# proto.net
KiCad netlist of a schematic drawn in EAGLE
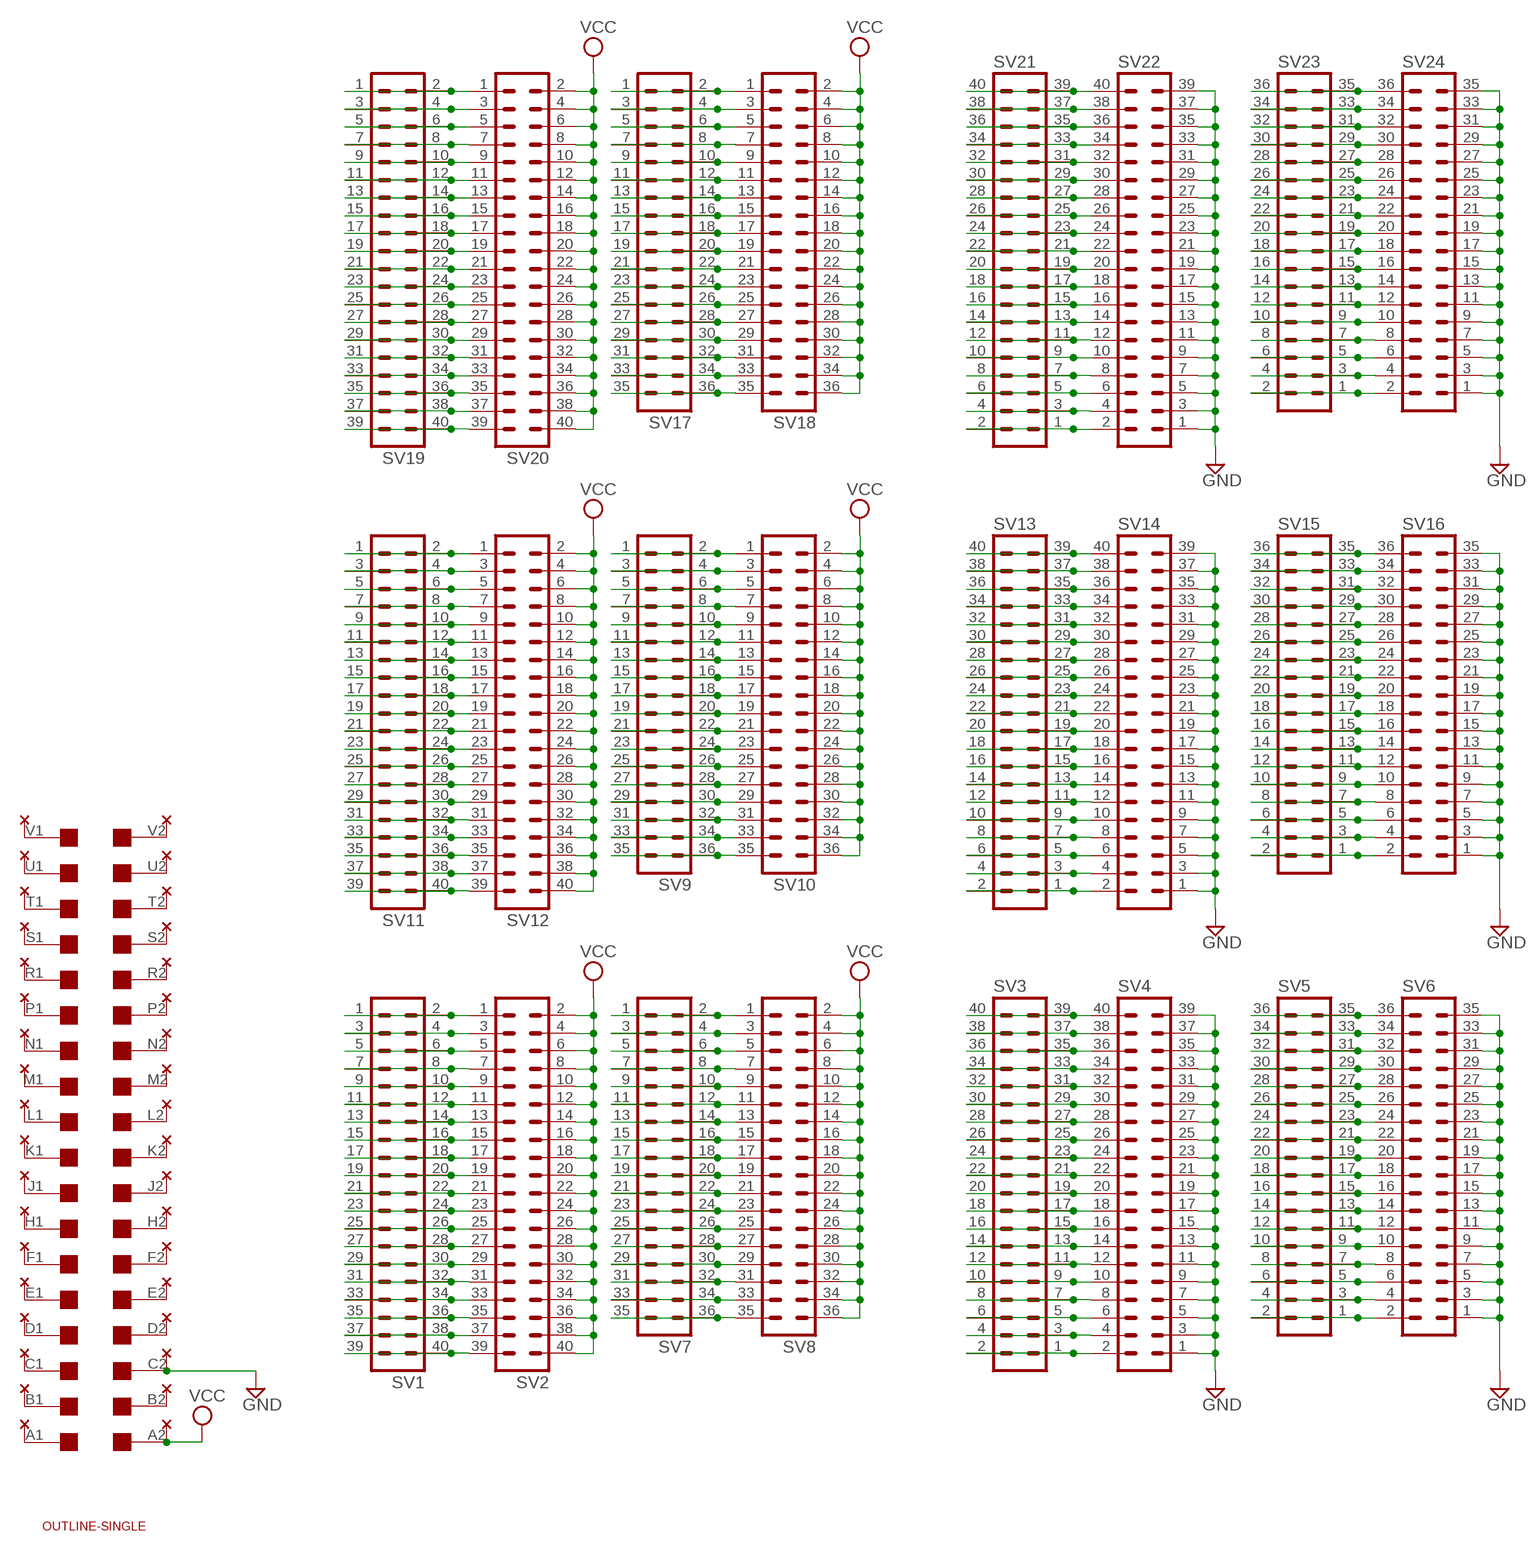
[diagram p0: schematic, sheet 1]

(export (version "E")
  (design (tool "Eeschema 10.0.6"))
  (components
    (comp (ref "SV1")
      (value "MA20-2")
      (footprint "eagle-import:MA20-2")
      (libsource (lib "eagle-import") (part "MA20-2"))
    )
    (comp (ref "SV2")
      (value "MA20-2")
      (footprint "eagle-import:MA20-2")
      (libsource (lib "eagle-import") (part "MA20-2"))
    )
    (comp (ref "SV3")
      (value "MA20-2")
      (footprint "eagle-import:MA20-2")
      (libsource (lib "eagle-import") (part "MA20-2"))
    )
    (comp (ref "SV4")
      (value "MA20-2")
      (footprint "eagle-import:MA20-2")
      (libsource (lib "eagle-import") (part "MA20-2"))
    )
    (comp (ref "SV5")
      (value "MA18-2")
      (footprint "eagle-import:MA18-2")
      (libsource (lib "eagle-import") (part "MA18-2"))
    )
    (comp (ref "SV6")
      (value "MA18-2")
      (footprint "eagle-import:MA18-2")
      (libsource (lib "eagle-import") (part "MA18-2"))
    )
    (comp (ref "SV7")
      (value "MA18-2")
      (footprint "eagle-import:MA18-2")
      (libsource (lib "eagle-import") (part "MA18-2"))
    )
    (comp (ref "SV8")
      (value "MA18-2")
      (footprint "eagle-import:MA18-2")
      (libsource (lib "eagle-import") (part "MA18-2"))
    )
    (comp (ref "SV9")
      (value "MA18-2")
      (footprint "eagle-import:MA18-2")
      (libsource (lib "eagle-import") (part "MA18-2"))
    )
    (comp (ref "SV10")
      (value "MA18-2")
      (footprint "eagle-import:MA18-2")
      (libsource (lib "eagle-import") (part "MA18-2"))
    )
    (comp (ref "SV11")
      (value "MA20-2")
      (footprint "eagle-import:MA20-2")
      (libsource (lib "eagle-import") (part "MA20-2"))
    )
    (comp (ref "SV12")
      (value "MA20-2")
      (footprint "eagle-import:MA20-2")
      (libsource (lib "eagle-import") (part "MA20-2"))
    )
    (comp (ref "SV13")
      (value "MA20-2")
      (footprint "eagle-import:MA20-2")
      (libsource (lib "eagle-import") (part "MA20-2"))
    )
    (comp (ref "SV14")
      (value "MA20-2")
      (footprint "eagle-import:MA20-2")
      (libsource (lib "eagle-import") (part "MA20-2"))
    )
    (comp (ref "SV15")
      (value "MA18-2")
      (footprint "eagle-import:MA18-2")
      (libsource (lib "eagle-import") (part "MA18-2"))
    )
    (comp (ref "SV16")
      (value "MA18-2")
      (footprint "eagle-import:MA18-2")
      (libsource (lib "eagle-import") (part "MA18-2"))
    )
    (comp (ref "SV17")
      (value "MA18-2")
      (footprint "eagle-import:MA18-2")
      (libsource (lib "eagle-import") (part "MA18-2"))
    )
    (comp (ref "SV18")
      (value "MA18-2")
      (footprint "eagle-import:MA18-2")
      (libsource (lib "eagle-import") (part "MA18-2"))
    )
    (comp (ref "SV19")
      (value "MA20-2")
      (footprint "eagle-import:MA20-2")
      (libsource (lib "eagle-import") (part "MA20-2"))
    )
    (comp (ref "SV20")
      (value "MA20-2")
      (footprint "eagle-import:MA20-2")
      (libsource (lib "eagle-import") (part "MA20-2"))
    )
    (comp (ref "SV21")
      (value "MA20-2")
      (footprint "eagle-import:MA20-2")
      (libsource (lib "eagle-import") (part "MA20-2"))
    )
    (comp (ref "SV22")
      (value "MA20-2")
      (footprint "eagle-import:MA20-2")
      (libsource (lib "eagle-import") (part "MA20-2"))
    )
    (comp (ref "SV23")
      (value "MA18-2")
      (footprint "eagle-import:MA18-2")
      (libsource (lib "eagle-import") (part "MA18-2"))
    )
    (comp (ref "SV24")
      (value "MA18-2")
      (footprint "eagle-import:MA18-2")
      (libsource (lib "eagle-import") (part "MA18-2"))
    )
    (comp (ref "U$1")
      (value "EDGE-2CONNECTOR")
      (footprint "eagle-import:EDGE-CON2")
      (libsource (lib "eagle-import") (part "EDGE-2CONNECTOR"))
    )
    (comp (ref "U$2")
      (value "OUTLINE-SINGLE")
      (footprint "eagle-import:SINGLE")
      (libsource (lib "eagle-import") (part "OUTLINE-SINGLE"))
    )
    (comp (ref "U$3")
      (value "THRU-HOLE2A")
      (footprint "eagle-import:THRU-HOLEA")
      (libsource (lib "eagle-import") (part "THRU-HOLE2A"))
    )
  )
  (nets
    (net (code "1") (name "GND") (class "Default")
      (node (ref "SV14") (pin "1") (pinfunction "1_1") (pintype "passive"))
      (node (ref "SV14") (pin "11") (pinfunction "11_11") (pintype "passive"))
      (node (ref "SV14") (pin "13") (pinfunction "13_13") (pintype "passive"))
      (node (ref "SV14") (pin "15") (pinfunction "15_15") (pintype "passive"))
      (node (ref "SV14") (pin "17") (pinfunction "17_17") (pintype "passive"))
      (node (ref "SV14") (pin "19") (pinfunction "19_19") (pintype "passive"))
      (node (ref "SV14") (pin "21") (pinfunction "21_21") (pintype "passive"))
      (node (ref "SV14") (pin "23") (pinfunction "23_23") (pintype "passive"))
      (node (ref "SV14") (pin "25") (pinfunction "25_25") (pintype "passive"))
      (node (ref "SV14") (pin "27") (pinfunction "27_27") (pintype "passive"))
      (node (ref "SV14") (pin "29") (pinfunction "29_29") (pintype "passive"))
      (node (ref "SV14") (pin "3") (pinfunction "3_3") (pintype "passive"))
      (node (ref "SV14") (pin "31") (pinfunction "31_31") (pintype "passive"))
      (node (ref "SV14") (pin "33") (pinfunction "33_33") (pintype "passive"))
      (node (ref "SV14") (pin "35") (pinfunction "35_35") (pintype "passive"))
      (node (ref "SV14") (pin "37") (pinfunction "37_37") (pintype "passive"))
      (node (ref "SV14") (pin "39") (pinfunction "39_39") (pintype "passive"))
      (node (ref "SV14") (pin "5") (pinfunction "5_5") (pintype "passive"))
      (node (ref "SV14") (pin "7") (pinfunction "7_7") (pintype "passive"))
      (node (ref "SV14") (pin "9") (pinfunction "9_9") (pintype "passive"))
      (node (ref "SV16") (pin "1") (pinfunction "1_1") (pintype "passive"))
      (node (ref "SV16") (pin "11") (pinfunction "11_11") (pintype "passive"))
      (node (ref "SV16") (pin "13") (pinfunction "13_13") (pintype "passive"))
      (node (ref "SV16") (pin "15") (pinfunction "15_15") (pintype "passive"))
      (node (ref "SV16") (pin "17") (pinfunction "17_17") (pintype "passive"))
      (node (ref "SV16") (pin "19") (pinfunction "19_19") (pintype "passive"))
      (node (ref "SV16") (pin "21") (pinfunction "21_21") (pintype "passive"))
      (node (ref "SV16") (pin "23") (pinfunction "23_23") (pintype "passive"))
      (node (ref "SV16") (pin "25") (pinfunction "25_25") (pintype "passive"))
      (node (ref "SV16") (pin "27") (pinfunction "27_27") (pintype "passive"))
      (node (ref "SV16") (pin "29") (pinfunction "29_29") (pintype "passive"))
      (node (ref "SV16") (pin "3") (pinfunction "3_3") (pintype "passive"))
      (node (ref "SV16") (pin "31") (pinfunction "31_31") (pintype "passive"))
      (node (ref "SV16") (pin "33") (pinfunction "33_33") (pintype "passive"))
      (node (ref "SV16") (pin "35") (pinfunction "35_35") (pintype "passive"))
      (node (ref "SV16") (pin "5") (pinfunction "5_5") (pintype "passive"))
      (node (ref "SV16") (pin "7") (pinfunction "7_7") (pintype "passive"))
      (node (ref "SV16") (pin "9") (pinfunction "9_9") (pintype "passive"))
      (node (ref "SV22") (pin "1") (pinfunction "1_1") (pintype "passive"))
      (node (ref "SV22") (pin "11") (pinfunction "11_11") (pintype "passive"))
      (node (ref "SV22") (pin "13") (pinfunction "13_13") (pintype "passive"))
      (node (ref "SV22") (pin "15") (pinfunction "15_15") (pintype "passive"))
      (node (ref "SV22") (pin "17") (pinfunction "17_17") (pintype "passive"))
      (node (ref "SV22") (pin "19") (pinfunction "19_19") (pintype "passive"))
      (node (ref "SV22") (pin "21") (pinfunction "21_21") (pintype "passive"))
      (node (ref "SV22") (pin "23") (pinfunction "23_23") (pintype "passive"))
      (node (ref "SV22") (pin "25") (pinfunction "25_25") (pintype "passive"))
      (node (ref "SV22") (pin "27") (pinfunction "27_27") (pintype "passive"))
      (node (ref "SV22") (pin "29") (pinfunction "29_29") (pintype "passive"))
      (node (ref "SV22") (pin "3") (pinfunction "3_3") (pintype "passive"))
      (node (ref "SV22") (pin "31") (pinfunction "31_31") (pintype "passive"))
      (node (ref "SV22") (pin "33") (pinfunction "33_33") (pintype "passive"))
      (node (ref "SV22") (pin "35") (pinfunction "35_35") (pintype "passive"))
      (node (ref "SV22") (pin "37") (pinfunction "37_37") (pintype "passive"))
      (node (ref "SV22") (pin "39") (pinfunction "39_39") (pintype "passive"))
      (node (ref "SV22") (pin "5") (pinfunction "5_5") (pintype "passive"))
      (node (ref "SV22") (pin "7") (pinfunction "7_7") (pintype "passive"))
      (node (ref "SV22") (pin "9") (pinfunction "9_9") (pintype "passive"))
      (node (ref "SV24") (pin "1") (pinfunction "1_1") (pintype "passive"))
      (node (ref "SV24") (pin "11") (pinfunction "11_11") (pintype "passive"))
      (node (ref "SV24") (pin "13") (pinfunction "13_13") (pintype "passive"))
      (node (ref "SV24") (pin "15") (pinfunction "15_15") (pintype "passive"))
      (node (ref "SV24") (pin "17") (pinfunction "17_17") (pintype "passive"))
      (node (ref "SV24") (pin "19") (pinfunction "19_19") (pintype "passive"))
      (node (ref "SV24") (pin "21") (pinfunction "21_21") (pintype "passive"))
      (node (ref "SV24") (pin "23") (pinfunction "23_23") (pintype "passive"))
      (node (ref "SV24") (pin "25") (pinfunction "25_25") (pintype "passive"))
      (node (ref "SV24") (pin "27") (pinfunction "27_27") (pintype "passive"))
      (node (ref "SV24") (pin "29") (pinfunction "29_29") (pintype "passive"))
      (node (ref "SV24") (pin "3") (pinfunction "3_3") (pintype "passive"))
      (node (ref "SV24") (pin "31") (pinfunction "31_31") (pintype "passive"))
      (node (ref "SV24") (pin "33") (pinfunction "33_33") (pintype "passive"))
      (node (ref "SV24") (pin "35") (pinfunction "35_35") (pintype "passive"))
      (node (ref "SV24") (pin "5") (pinfunction "5_5") (pintype "passive"))
      (node (ref "SV24") (pin "7") (pinfunction "7_7") (pintype "passive"))
      (node (ref "SV24") (pin "9") (pinfunction "9_9") (pintype "passive"))
      (node (ref "SV4") (pin "1") (pinfunction "1_1") (pintype "passive"))
      (node (ref "SV4") (pin "11") (pinfunction "11_11") (pintype "passive"))
      (node (ref "SV4") (pin "13") (pinfunction "13_13") (pintype "passive"))
      (node (ref "SV4") (pin "15") (pinfunction "15_15") (pintype "passive"))
      (node (ref "SV4") (pin "17") (pinfunction "17_17") (pintype "passive"))
      (node (ref "SV4") (pin "19") (pinfunction "19_19") (pintype "passive"))
      (node (ref "SV4") (pin "21") (pinfunction "21_21") (pintype "passive"))
      (node (ref "SV4") (pin "23") (pinfunction "23_23") (pintype "passive"))
      (node (ref "SV4") (pin "25") (pinfunction "25_25") (pintype "passive"))
      (node (ref "SV4") (pin "27") (pinfunction "27_27") (pintype "passive"))
      (node (ref "SV4") (pin "29") (pinfunction "29_29") (pintype "passive"))
      (node (ref "SV4") (pin "3") (pinfunction "3_3") (pintype "passive"))
      (node (ref "SV4") (pin "31") (pinfunction "31_31") (pintype "passive"))
      (node (ref "SV4") (pin "33") (pinfunction "33_33") (pintype "passive"))
      (node (ref "SV4") (pin "35") (pinfunction "35_35") (pintype "passive"))
      (node (ref "SV4") (pin "37") (pinfunction "37_37") (pintype "passive"))
      (node (ref "SV4") (pin "39") (pinfunction "39_39") (pintype "passive"))
      (node (ref "SV4") (pin "5") (pinfunction "5_5") (pintype "passive"))
      (node (ref "SV4") (pin "7") (pinfunction "7_7") (pintype "passive"))
      (node (ref "SV4") (pin "9") (pinfunction "9_9") (pintype "passive"))
      (node (ref "SV6") (pin "1") (pinfunction "1_1") (pintype "passive"))
      (node (ref "SV6") (pin "11") (pinfunction "11_11") (pintype "passive"))
      (node (ref "SV6") (pin "13") (pinfunction "13_13") (pintype "passive"))
      (node (ref "SV6") (pin "15") (pinfunction "15_15") (pintype "passive"))
      (node (ref "SV6") (pin "17") (pinfunction "17_17") (pintype "passive"))
      (node (ref "SV6") (pin "19") (pinfunction "19_19") (pintype "passive"))
      (node (ref "SV6") (pin "21") (pinfunction "21_21") (pintype "passive"))
      (node (ref "SV6") (pin "23") (pinfunction "23_23") (pintype "passive"))
      (node (ref "SV6") (pin "25") (pinfunction "25_25") (pintype "passive"))
      (node (ref "SV6") (pin "27") (pinfunction "27_27") (pintype "passive"))
      (node (ref "SV6") (pin "29") (pinfunction "29_29") (pintype "passive"))
      (node (ref "SV6") (pin "3") (pinfunction "3_3") (pintype "passive"))
      (node (ref "SV6") (pin "31") (pinfunction "31_31") (pintype "passive"))
      (node (ref "SV6") (pin "33") (pinfunction "33_33") (pintype "passive"))
      (node (ref "SV6") (pin "35") (pinfunction "35_35") (pintype "passive"))
      (node (ref "SV6") (pin "5") (pinfunction "5_5") (pintype "passive"))
      (node (ref "SV6") (pin "7") (pinfunction "7_7") (pintype "passive"))
      (node (ref "SV6") (pin "9") (pinfunction "9_9") (pintype "passive"))
      (node (ref "U$1") (pin "C2") (pinfunction "1_C2") (pintype "bidirectional"))
      (node (ref "U$3") (pin "C2") (pinfunction "P$1_C2") (pintype "passive"))
    )
    (net (code "2") (name "Net-(SV1-Pad1)") (class "Default")
      (node (ref "SV1") (pin "1") (pinfunction "1_1") (pintype "passive"))
      (node (ref "SV1") (pin "2") (pinfunction "2_2") (pintype "passive"))
      (node (ref "SV2") (pin "1") (pinfunction "1_1") (pintype "passive"))
    )
    (net (code "3") (name "Net-(SV1-Pad3)") (class "Default")
      (node (ref "SV1") (pin "3") (pinfunction "3_3") (pintype "passive"))
      (node (ref "SV1") (pin "4") (pinfunction "4_4") (pintype "passive"))
      (node (ref "SV2") (pin "3") (pinfunction "3_3") (pintype "passive"))
    )
    (net (code "4") (name "Net-(SV1-Pad5)") (class "Default")
      (node (ref "SV1") (pin "5") (pinfunction "5_5") (pintype "passive"))
      (node (ref "SV1") (pin "6") (pinfunction "6_6") (pintype "passive"))
      (node (ref "SV2") (pin "5") (pinfunction "5_5") (pintype "passive"))
    )
    (net (code "5") (name "Net-(SV1-Pad7)") (class "Default")
      (node (ref "SV1") (pin "7") (pinfunction "7_7") (pintype "passive"))
      (node (ref "SV1") (pin "8") (pinfunction "8_8") (pintype "passive"))
      (node (ref "SV2") (pin "7") (pinfunction "7_7") (pintype "passive"))
    )
    (net (code "6") (name "Net-(SV1-Pad10)") (class "Default")
      (node (ref "SV1") (pin "10") (pinfunction "10_10") (pintype "passive"))
      (node (ref "SV1") (pin "9") (pinfunction "9_9") (pintype "passive"))
      (node (ref "SV2") (pin "9") (pinfunction "9_9") (pintype "passive"))
    )
    (net (code "7") (name "Net-(SV1-Pad11)") (class "Default")
      (node (ref "SV1") (pin "11") (pinfunction "11_11") (pintype "passive"))
      (node (ref "SV1") (pin "12") (pinfunction "12_12") (pintype "passive"))
      (node (ref "SV2") (pin "11") (pinfunction "11_11") (pintype "passive"))
    )
    (net (code "8") (name "Net-(SV1-Pad13)") (class "Default")
      (node (ref "SV1") (pin "13") (pinfunction "13_13") (pintype "passive"))
      (node (ref "SV1") (pin "14") (pinfunction "14_14") (pintype "passive"))
      (node (ref "SV2") (pin "13") (pinfunction "13_13") (pintype "passive"))
    )
    (net (code "9") (name "Net-(SV1-Pad15)") (class "Default")
      (node (ref "SV1") (pin "15") (pinfunction "15_15") (pintype "passive"))
      (node (ref "SV1") (pin "16") (pinfunction "16_16") (pintype "passive"))
      (node (ref "SV2") (pin "15") (pinfunction "15_15") (pintype "passive"))
    )
    (net (code "10") (name "Net-(SV1-Pad17)") (class "Default")
      (node (ref "SV1") (pin "17") (pinfunction "17_17") (pintype "passive"))
      (node (ref "SV1") (pin "18") (pinfunction "18_18") (pintype "passive"))
      (node (ref "SV2") (pin "17") (pinfunction "17_17") (pintype "passive"))
    )
    (net (code "11") (name "Net-(SV1-Pad19)") (class "Default")
      (node (ref "SV1") (pin "19") (pinfunction "19_19") (pintype "passive"))
      (node (ref "SV1") (pin "20") (pinfunction "20_20") (pintype "passive"))
      (node (ref "SV2") (pin "19") (pinfunction "19_19") (pintype "passive"))
    )
    (net (code "12") (name "Net-(SV1-Pad21)") (class "Default")
      (node (ref "SV1") (pin "21") (pinfunction "21_21") (pintype "passive"))
      (node (ref "SV1") (pin "22") (pinfunction "22_22") (pintype "passive"))
      (node (ref "SV2") (pin "21") (pinfunction "21_21") (pintype "passive"))
    )
    (net (code "13") (name "Net-(SV1-Pad23)") (class "Default")
      (node (ref "SV1") (pin "23") (pinfunction "23_23") (pintype "passive"))
      (node (ref "SV1") (pin "24") (pinfunction "24_24") (pintype "passive"))
      (node (ref "SV2") (pin "23") (pinfunction "23_23") (pintype "passive"))
    )
    (net (code "14") (name "Net-(SV1-Pad25)") (class "Default")
      (node (ref "SV1") (pin "25") (pinfunction "25_25") (pintype "passive"))
      (node (ref "SV1") (pin "26") (pinfunction "26_26") (pintype "passive"))
      (node (ref "SV2") (pin "25") (pinfunction "25_25") (pintype "passive"))
    )
    (net (code "15") (name "Net-(SV1-Pad27)") (class "Default")
      (node (ref "SV1") (pin "27") (pinfunction "27_27") (pintype "passive"))
      (node (ref "SV1") (pin "28") (pinfunction "28_28") (pintype "passive"))
      (node (ref "SV2") (pin "27") (pinfunction "27_27") (pintype "passive"))
    )
    (net (code "16") (name "Net-(SV1-Pad29)") (class "Default")
      (node (ref "SV1") (pin "29") (pinfunction "29_29") (pintype "passive"))
      (node (ref "SV1") (pin "30") (pinfunction "30_30") (pintype "passive"))
      (node (ref "SV2") (pin "29") (pinfunction "29_29") (pintype "passive"))
    )
    (net (code "17") (name "Net-(SV1-Pad31)") (class "Default")
      (node (ref "SV1") (pin "31") (pinfunction "31_31") (pintype "passive"))
      (node (ref "SV1") (pin "32") (pinfunction "32_32") (pintype "passive"))
      (node (ref "SV2") (pin "31") (pinfunction "31_31") (pintype "passive"))
    )
    (net (code "18") (name "Net-(SV1-Pad33)") (class "Default")
      (node (ref "SV1") (pin "33") (pinfunction "33_33") (pintype "passive"))
      (node (ref "SV1") (pin "34") (pinfunction "34_34") (pintype "passive"))
      (node (ref "SV2") (pin "33") (pinfunction "33_33") (pintype "passive"))
    )
    (net (code "19") (name "Net-(SV1-Pad35)") (class "Default")
      (node (ref "SV1") (pin "35") (pinfunction "35_35") (pintype "passive"))
      (node (ref "SV1") (pin "36") (pinfunction "36_36") (pintype "passive"))
      (node (ref "SV2") (pin "35") (pinfunction "35_35") (pintype "passive"))
    )
    (net (code "20") (name "Net-(SV1-Pad37)") (class "Default")
      (node (ref "SV1") (pin "37") (pinfunction "37_37") (pintype "passive"))
      (node (ref "SV1") (pin "38") (pinfunction "38_38") (pintype "passive"))
      (node (ref "SV2") (pin "37") (pinfunction "37_37") (pintype "passive"))
    )
    (net (code "21") (name "Net-(SV1-Pad39)") (class "Default")
      (node (ref "SV1") (pin "39") (pinfunction "39_39") (pintype "passive"))
      (node (ref "SV1") (pin "40") (pinfunction "40_40") (pintype "passive"))
      (node (ref "SV2") (pin "39") (pinfunction "39_39") (pintype "passive"))
    )
    (net (code "22") (name "Net-(SV3-Pad1)") (class "Default")
      (node (ref "SV3") (pin "1") (pinfunction "1_1") (pintype "passive"))
      (node (ref "SV3") (pin "2") (pinfunction "2_2") (pintype "passive"))
      (node (ref "SV4") (pin "2") (pinfunction "2_2") (pintype "passive"))
    )
    (net (code "23") (name "Net-(SV3-Pad3)") (class "Default")
      (node (ref "SV3") (pin "3") (pinfunction "3_3") (pintype "passive"))
      (node (ref "SV3") (pin "4") (pinfunction "4_4") (pintype "passive"))
      (node (ref "SV4") (pin "4") (pinfunction "4_4") (pintype "passive"))
    )
    (net (code "24") (name "Net-(SV3-Pad5)") (class "Default")
      (node (ref "SV3") (pin "5") (pinfunction "5_5") (pintype "passive"))
      (node (ref "SV3") (pin "6") (pinfunction "6_6") (pintype "passive"))
      (node (ref "SV4") (pin "6") (pinfunction "6_6") (pintype "passive"))
    )
    (net (code "25") (name "Net-(SV3-Pad7)") (class "Default")
      (node (ref "SV3") (pin "7") (pinfunction "7_7") (pintype "passive"))
      (node (ref "SV3") (pin "8") (pinfunction "8_8") (pintype "passive"))
      (node (ref "SV4") (pin "8") (pinfunction "8_8") (pintype "passive"))
    )
    (net (code "26") (name "Net-(SV3-Pad10)") (class "Default")
      (node (ref "SV3") (pin "10") (pinfunction "10_10") (pintype "passive"))
      (node (ref "SV3") (pin "9") (pinfunction "9_9") (pintype "passive"))
      (node (ref "SV4") (pin "10") (pinfunction "10_10") (pintype "passive"))
    )
    (net (code "27") (name "Net-(SV3-Pad11)") (class "Default")
      (node (ref "SV3") (pin "11") (pinfunction "11_11") (pintype "passive"))
      (node (ref "SV3") (pin "12") (pinfunction "12_12") (pintype "passive"))
      (node (ref "SV4") (pin "12") (pinfunction "12_12") (pintype "passive"))
    )
    (net (code "28") (name "Net-(SV3-Pad13)") (class "Default")
      (node (ref "SV3") (pin "13") (pinfunction "13_13") (pintype "passive"))
      (node (ref "SV3") (pin "14") (pinfunction "14_14") (pintype "passive"))
      (node (ref "SV4") (pin "14") (pinfunction "14_14") (pintype "passive"))
    )
    (net (code "29") (name "Net-(SV3-Pad15)") (class "Default")
      (node (ref "SV3") (pin "15") (pinfunction "15_15") (pintype "passive"))
      (node (ref "SV3") (pin "16") (pinfunction "16_16") (pintype "passive"))
      (node (ref "SV4") (pin "16") (pinfunction "16_16") (pintype "passive"))
    )
    (net (code "30") (name "Net-(SV3-Pad17)") (class "Default")
      (node (ref "SV3") (pin "17") (pinfunction "17_17") (pintype "passive"))
      (node (ref "SV3") (pin "18") (pinfunction "18_18") (pintype "passive"))
      (node (ref "SV4") (pin "18") (pinfunction "18_18") (pintype "passive"))
    )
    (net (code "31") (name "Net-(SV3-Pad19)") (class "Default")
      (node (ref "SV3") (pin "19") (pinfunction "19_19") (pintype "passive"))
      (node (ref "SV3") (pin "20") (pinfunction "20_20") (pintype "passive"))
      (node (ref "SV4") (pin "20") (pinfunction "20_20") (pintype "passive"))
    )
    (net (code "32") (name "Net-(SV3-Pad21)") (class "Default")
      (node (ref "SV3") (pin "21") (pinfunction "21_21") (pintype "passive"))
      (node (ref "SV3") (pin "22") (pinfunction "22_22") (pintype "passive"))
      (node (ref "SV4") (pin "22") (pinfunction "22_22") (pintype "passive"))
    )
    (net (code "33") (name "Net-(SV3-Pad23)") (class "Default")
      (node (ref "SV3") (pin "23") (pinfunction "23_23") (pintype "passive"))
      (node (ref "SV3") (pin "24") (pinfunction "24_24") (pintype "passive"))
      (node (ref "SV4") (pin "24") (pinfunction "24_24") (pintype "passive"))
    )
    (net (code "34") (name "Net-(SV3-Pad25)") (class "Default")
      (node (ref "SV3") (pin "25") (pinfunction "25_25") (pintype "passive"))
      (node (ref "SV3") (pin "26") (pinfunction "26_26") (pintype "passive"))
      (node (ref "SV4") (pin "26") (pinfunction "26_26") (pintype "passive"))
    )
    (net (code "35") (name "Net-(SV3-Pad27)") (class "Default")
      (node (ref "SV3") (pin "27") (pinfunction "27_27") (pintype "passive"))
      (node (ref "SV3") (pin "28") (pinfunction "28_28") (pintype "passive"))
      (node (ref "SV4") (pin "28") (pinfunction "28_28") (pintype "passive"))
    )
    (net (code "36") (name "Net-(SV3-Pad29)") (class "Default")
      (node (ref "SV3") (pin "29") (pinfunction "29_29") (pintype "passive"))
      (node (ref "SV3") (pin "30") (pinfunction "30_30") (pintype "passive"))
      (node (ref "SV4") (pin "30") (pinfunction "30_30") (pintype "passive"))
    )
    (net (code "37") (name "Net-(SV3-Pad31)") (class "Default")
      (node (ref "SV3") (pin "31") (pinfunction "31_31") (pintype "passive"))
      (node (ref "SV3") (pin "32") (pinfunction "32_32") (pintype "passive"))
      (node (ref "SV4") (pin "32") (pinfunction "32_32") (pintype "passive"))
    )
    (net (code "38") (name "Net-(SV3-Pad33)") (class "Default")
      (node (ref "SV3") (pin "33") (pinfunction "33_33") (pintype "passive"))
      (node (ref "SV3") (pin "34") (pinfunction "34_34") (pintype "passive"))
      (node (ref "SV4") (pin "34") (pinfunction "34_34") (pintype "passive"))
    )
    (net (code "39") (name "Net-(SV3-Pad35)") (class "Default")
      (node (ref "SV3") (pin "35") (pinfunction "35_35") (pintype "passive"))
      (node (ref "SV3") (pin "36") (pinfunction "36_36") (pintype "passive"))
      (node (ref "SV4") (pin "36") (pinfunction "36_36") (pintype "passive"))
    )
    (net (code "40") (name "Net-(SV3-Pad37)") (class "Default")
      (node (ref "SV3") (pin "37") (pinfunction "37_37") (pintype "passive"))
      (node (ref "SV3") (pin "38") (pinfunction "38_38") (pintype "passive"))
      (node (ref "SV4") (pin "38") (pinfunction "38_38") (pintype "passive"))
    )
    (net (code "41") (name "Net-(SV3-Pad39)") (class "Default")
      (node (ref "SV3") (pin "39") (pinfunction "39_39") (pintype "passive"))
      (node (ref "SV3") (pin "40") (pinfunction "40_40") (pintype "passive"))
      (node (ref "SV4") (pin "40") (pinfunction "40_40") (pintype "passive"))
    )
    (net (code "42") (name "Net-(SV5-Pad1)") (class "Default")
      (node (ref "SV5") (pin "1") (pinfunction "1_1") (pintype "passive"))
      (node (ref "SV5") (pin "2") (pinfunction "2_2") (pintype "passive"))
      (node (ref "SV6") (pin "2") (pinfunction "2_2") (pintype "passive"))
    )
    (net (code "43") (name "Net-(SV5-Pad3)") (class "Default")
      (node (ref "SV5") (pin "3") (pinfunction "3_3") (pintype "passive"))
      (node (ref "SV5") (pin "4") (pinfunction "4_4") (pintype "passive"))
      (node (ref "SV6") (pin "4") (pinfunction "4_4") (pintype "passive"))
    )
    (net (code "44") (name "Net-(SV5-Pad5)") (class "Default")
      (node (ref "SV5") (pin "5") (pinfunction "5_5") (pintype "passive"))
      (node (ref "SV5") (pin "6") (pinfunction "6_6") (pintype "passive"))
      (node (ref "SV6") (pin "6") (pinfunction "6_6") (pintype "passive"))
    )
    (net (code "45") (name "Net-(SV5-Pad7)") (class "Default")
      (node (ref "SV5") (pin "7") (pinfunction "7_7") (pintype "passive"))
      (node (ref "SV5") (pin "8") (pinfunction "8_8") (pintype "passive"))
      (node (ref "SV6") (pin "8") (pinfunction "8_8") (pintype "passive"))
    )
    (net (code "46") (name "Net-(SV5-Pad10)") (class "Default")
      (node (ref "SV5") (pin "10") (pinfunction "10_10") (pintype "passive"))
      (node (ref "SV5") (pin "9") (pinfunction "9_9") (pintype "passive"))
      (node (ref "SV6") (pin "10") (pinfunction "10_10") (pintype "passive"))
    )
    (net (code "47") (name "Net-(SV5-Pad11)") (class "Default")
      (node (ref "SV5") (pin "11") (pinfunction "11_11") (pintype "passive"))
      (node (ref "SV5") (pin "12") (pinfunction "12_12") (pintype "passive"))
      (node (ref "SV6") (pin "12") (pinfunction "12_12") (pintype "passive"))
    )
    (net (code "48") (name "Net-(SV5-Pad13)") (class "Default")
      (node (ref "SV5") (pin "13") (pinfunction "13_13") (pintype "passive"))
      (node (ref "SV5") (pin "14") (pinfunction "14_14") (pintype "passive"))
      (node (ref "SV6") (pin "14") (pinfunction "14_14") (pintype "passive"))
    )
    (net (code "49") (name "Net-(SV5-Pad15)") (class "Default")
      (node (ref "SV5") (pin "15") (pinfunction "15_15") (pintype "passive"))
      (node (ref "SV5") (pin "16") (pinfunction "16_16") (pintype "passive"))
      (node (ref "SV6") (pin "16") (pinfunction "16_16") (pintype "passive"))
    )
    (net (code "50") (name "Net-(SV5-Pad17)") (class "Default")
      (node (ref "SV5") (pin "17") (pinfunction "17_17") (pintype "passive"))
      (node (ref "SV5") (pin "18") (pinfunction "18_18") (pintype "passive"))
      (node (ref "SV6") (pin "18") (pinfunction "18_18") (pintype "passive"))
    )
    (net (code "51") (name "Net-(SV5-Pad19)") (class "Default")
      (node (ref "SV5") (pin "19") (pinfunction "19_19") (pintype "passive"))
      (node (ref "SV5") (pin "20") (pinfunction "20_20") (pintype "passive"))
      (node (ref "SV6") (pin "20") (pinfunction "20_20") (pintype "passive"))
    )
    (net (code "52") (name "Net-(SV5-Pad21)") (class "Default")
      (node (ref "SV5") (pin "21") (pinfunction "21_21") (pintype "passive"))
      (node (ref "SV5") (pin "22") (pinfunction "22_22") (pintype "passive"))
      (node (ref "SV6") (pin "22") (pinfunction "22_22") (pintype "passive"))
    )
    (net (code "53") (name "Net-(SV5-Pad23)") (class "Default")
      (node (ref "SV5") (pin "23") (pinfunction "23_23") (pintype "passive"))
      (node (ref "SV5") (pin "24") (pinfunction "24_24") (pintype "passive"))
      (node (ref "SV6") (pin "24") (pinfunction "24_24") (pintype "passive"))
    )
    (net (code "54") (name "Net-(SV5-Pad25)") (class "Default")
      (node (ref "SV5") (pin "25") (pinfunction "25_25") (pintype "passive"))
      (node (ref "SV5") (pin "26") (pinfunction "26_26") (pintype "passive"))
      (node (ref "SV6") (pin "26") (pinfunction "26_26") (pintype "passive"))
    )
    (net (code "55") (name "Net-(SV5-Pad27)") (class "Default")
      (node (ref "SV5") (pin "27") (pinfunction "27_27") (pintype "passive"))
      (node (ref "SV5") (pin "28") (pinfunction "28_28") (pintype "passive"))
      (node (ref "SV6") (pin "28") (pinfunction "28_28") (pintype "passive"))
    )
    (net (code "56") (name "Net-(SV5-Pad29)") (class "Default")
      (node (ref "SV5") (pin "29") (pinfunction "29_29") (pintype "passive"))
      (node (ref "SV5") (pin "30") (pinfunction "30_30") (pintype "passive"))
      (node (ref "SV6") (pin "30") (pinfunction "30_30") (pintype "passive"))
    )
    (net (code "57") (name "Net-(SV5-Pad31)") (class "Default")
      (node (ref "SV5") (pin "31") (pinfunction "31_31") (pintype "passive"))
      (node (ref "SV5") (pin "32") (pinfunction "32_32") (pintype "passive"))
      (node (ref "SV6") (pin "32") (pinfunction "32_32") (pintype "passive"))
    )
    (net (code "58") (name "Net-(SV5-Pad33)") (class "Default")
      (node (ref "SV5") (pin "33") (pinfunction "33_33") (pintype "passive"))
      (node (ref "SV5") (pin "34") (pinfunction "34_34") (pintype "passive"))
      (node (ref "SV6") (pin "34") (pinfunction "34_34") (pintype "passive"))
    )
    (net (code "59") (name "Net-(SV5-Pad35)") (class "Default")
      (node (ref "SV5") (pin "35") (pinfunction "35_35") (pintype "passive"))
      (node (ref "SV5") (pin "36") (pinfunction "36_36") (pintype "passive"))
      (node (ref "SV6") (pin "36") (pinfunction "36_36") (pintype "passive"))
    )
    (net (code "60") (name "Net-(SV7-Pad1)") (class "Default")
      (node (ref "SV7") (pin "1") (pinfunction "1_1") (pintype "passive"))
      (node (ref "SV7") (pin "2") (pinfunction "2_2") (pintype "passive"))
      (node (ref "SV8") (pin "1") (pinfunction "1_1") (pintype "passive"))
    )
    (net (code "61") (name "Net-(SV7-Pad3)") (class "Default")
      (node (ref "SV7") (pin "3") (pinfunction "3_3") (pintype "passive"))
      (node (ref "SV7") (pin "4") (pinfunction "4_4") (pintype "passive"))
      (node (ref "SV8") (pin "3") (pinfunction "3_3") (pintype "passive"))
    )
    (net (code "62") (name "Net-(SV7-Pad5)") (class "Default")
      (node (ref "SV7") (pin "5") (pinfunction "5_5") (pintype "passive"))
      (node (ref "SV7") (pin "6") (pinfunction "6_6") (pintype "passive"))
      (node (ref "SV8") (pin "5") (pinfunction "5_5") (pintype "passive"))
    )
    (net (code "63") (name "Net-(SV7-Pad7)") (class "Default")
      (node (ref "SV7") (pin "7") (pinfunction "7_7") (pintype "passive"))
      (node (ref "SV7") (pin "8") (pinfunction "8_8") (pintype "passive"))
      (node (ref "SV8") (pin "7") (pinfunction "7_7") (pintype "passive"))
    )
    (net (code "64") (name "Net-(SV7-Pad10)") (class "Default")
      (node (ref "SV7") (pin "10") (pinfunction "10_10") (pintype "passive"))
      (node (ref "SV7") (pin "9") (pinfunction "9_9") (pintype "passive"))
      (node (ref "SV8") (pin "9") (pinfunction "9_9") (pintype "passive"))
    )
    (net (code "65") (name "Net-(SV7-Pad11)") (class "Default")
      (node (ref "SV7") (pin "11") (pinfunction "11_11") (pintype "passive"))
      (node (ref "SV7") (pin "12") (pinfunction "12_12") (pintype "passive"))
      (node (ref "SV8") (pin "11") (pinfunction "11_11") (pintype "passive"))
    )
    (net (code "66") (name "Net-(SV7-Pad13)") (class "Default")
      (node (ref "SV7") (pin "13") (pinfunction "13_13") (pintype "passive"))
      (node (ref "SV7") (pin "14") (pinfunction "14_14") (pintype "passive"))
      (node (ref "SV8") (pin "13") (pinfunction "13_13") (pintype "passive"))
    )
    (net (code "67") (name "Net-(SV7-Pad15)") (class "Default")
      (node (ref "SV7") (pin "15") (pinfunction "15_15") (pintype "passive"))
      (node (ref "SV7") (pin "16") (pinfunction "16_16") (pintype "passive"))
      (node (ref "SV8") (pin "15") (pinfunction "15_15") (pintype "passive"))
    )
    (net (code "68") (name "Net-(SV7-Pad17)") (class "Default")
      (node (ref "SV7") (pin "17") (pinfunction "17_17") (pintype "passive"))
      (node (ref "SV7") (pin "18") (pinfunction "18_18") (pintype "passive"))
      (node (ref "SV8") (pin "17") (pinfunction "17_17") (pintype "passive"))
    )
    (net (code "69") (name "Net-(SV7-Pad19)") (class "Default")
      (node (ref "SV7") (pin "19") (pinfunction "19_19") (pintype "passive"))
      (node (ref "SV7") (pin "20") (pinfunction "20_20") (pintype "passive"))
      (node (ref "SV8") (pin "19") (pinfunction "19_19") (pintype "passive"))
    )
    (net (code "70") (name "Net-(SV7-Pad21)") (class "Default")
      (node (ref "SV7") (pin "21") (pinfunction "21_21") (pintype "passive"))
      (node (ref "SV7") (pin "22") (pinfunction "22_22") (pintype "passive"))
      (node (ref "SV8") (pin "21") (pinfunction "21_21") (pintype "passive"))
    )
    (net (code "71") (name "Net-(SV7-Pad23)") (class "Default")
      (node (ref "SV7") (pin "23") (pinfunction "23_23") (pintype "passive"))
      (node (ref "SV7") (pin "24") (pinfunction "24_24") (pintype "passive"))
      (node (ref "SV8") (pin "23") (pinfunction "23_23") (pintype "passive"))
    )
    (net (code "72") (name "Net-(SV7-Pad25)") (class "Default")
      (node (ref "SV7") (pin "25") (pinfunction "25_25") (pintype "passive"))
      (node (ref "SV7") (pin "26") (pinfunction "26_26") (pintype "passive"))
      (node (ref "SV8") (pin "25") (pinfunction "25_25") (pintype "passive"))
    )
    (net (code "73") (name "Net-(SV7-Pad27)") (class "Default")
      (node (ref "SV7") (pin "27") (pinfunction "27_27") (pintype "passive"))
      (node (ref "SV7") (pin "28") (pinfunction "28_28") (pintype "passive"))
      (node (ref "SV8") (pin "27") (pinfunction "27_27") (pintype "passive"))
    )
    (net (code "74") (name "Net-(SV7-Pad29)") (class "Default")
      (node (ref "SV7") (pin "29") (pinfunction "29_29") (pintype "passive"))
      (node (ref "SV7") (pin "30") (pinfunction "30_30") (pintype "passive"))
      (node (ref "SV8") (pin "29") (pinfunction "29_29") (pintype "passive"))
    )
    (net (code "75") (name "Net-(SV7-Pad31)") (class "Default")
      (node (ref "SV7") (pin "31") (pinfunction "31_31") (pintype "passive"))
      (node (ref "SV7") (pin "32") (pinfunction "32_32") (pintype "passive"))
      (node (ref "SV8") (pin "31") (pinfunction "31_31") (pintype "passive"))
    )
    (net (code "76") (name "Net-(SV7-Pad33)") (class "Default")
      (node (ref "SV7") (pin "33") (pinfunction "33_33") (pintype "passive"))
      (node (ref "SV7") (pin "34") (pinfunction "34_34") (pintype "passive"))
      (node (ref "SV8") (pin "33") (pinfunction "33_33") (pintype "passive"))
    )
    (net (code "77") (name "Net-(SV7-Pad35)") (class "Default")
      (node (ref "SV7") (pin "35") (pinfunction "35_35") (pintype "passive"))
      (node (ref "SV7") (pin "36") (pinfunction "36_36") (pintype "passive"))
      (node (ref "SV8") (pin "35") (pinfunction "35_35") (pintype "passive"))
    )
    (net (code "78") (name "Net-(SV10-Pad1)") (class "Default")
      (node (ref "SV10") (pin "1") (pinfunction "1_1") (pintype "passive"))
      (node (ref "SV9") (pin "1") (pinfunction "1_1") (pintype "passive"))
      (node (ref "SV9") (pin "2") (pinfunction "2_2") (pintype "passive"))
    )
    (net (code "79") (name "Net-(SV10-Pad3)") (class "Default")
      (node (ref "SV10") (pin "3") (pinfunction "3_3") (pintype "passive"))
      (node (ref "SV9") (pin "3") (pinfunction "3_3") (pintype "passive"))
      (node (ref "SV9") (pin "4") (pinfunction "4_4") (pintype "passive"))
    )
    (net (code "80") (name "Net-(SV10-Pad5)") (class "Default")
      (node (ref "SV10") (pin "5") (pinfunction "5_5") (pintype "passive"))
      (node (ref "SV9") (pin "5") (pinfunction "5_5") (pintype "passive"))
      (node (ref "SV9") (pin "6") (pinfunction "6_6") (pintype "passive"))
    )
    (net (code "81") (name "Net-(SV10-Pad7)") (class "Default")
      (node (ref "SV10") (pin "7") (pinfunction "7_7") (pintype "passive"))
      (node (ref "SV9") (pin "7") (pinfunction "7_7") (pintype "passive"))
      (node (ref "SV9") (pin "8") (pinfunction "8_8") (pintype "passive"))
    )
    (net (code "82") (name "Net-(SV10-Pad9)") (class "Default")
      (node (ref "SV10") (pin "9") (pinfunction "9_9") (pintype "passive"))
      (node (ref "SV9") (pin "10") (pinfunction "10_10") (pintype "passive"))
      (node (ref "SV9") (pin "9") (pinfunction "9_9") (pintype "passive"))
    )
    (net (code "83") (name "Net-(SV10-Pad11)") (class "Default")
      (node (ref "SV10") (pin "11") (pinfunction "11_11") (pintype "passive"))
      (node (ref "SV9") (pin "11") (pinfunction "11_11") (pintype "passive"))
      (node (ref "SV9") (pin "12") (pinfunction "12_12") (pintype "passive"))
    )
    (net (code "84") (name "Net-(SV10-Pad13)") (class "Default")
      (node (ref "SV10") (pin "13") (pinfunction "13_13") (pintype "passive"))
      (node (ref "SV9") (pin "13") (pinfunction "13_13") (pintype "passive"))
      (node (ref "SV9") (pin "14") (pinfunction "14_14") (pintype "passive"))
    )
    (net (code "85") (name "Net-(SV10-Pad15)") (class "Default")
      (node (ref "SV10") (pin "15") (pinfunction "15_15") (pintype "passive"))
      (node (ref "SV9") (pin "15") (pinfunction "15_15") (pintype "passive"))
      (node (ref "SV9") (pin "16") (pinfunction "16_16") (pintype "passive"))
    )
    (net (code "86") (name "Net-(SV10-Pad17)") (class "Default")
      (node (ref "SV10") (pin "17") (pinfunction "17_17") (pintype "passive"))
      (node (ref "SV9") (pin "17") (pinfunction "17_17") (pintype "passive"))
      (node (ref "SV9") (pin "18") (pinfunction "18_18") (pintype "passive"))
    )
    (net (code "87") (name "Net-(SV10-Pad19)") (class "Default")
      (node (ref "SV10") (pin "19") (pinfunction "19_19") (pintype "passive"))
      (node (ref "SV9") (pin "19") (pinfunction "19_19") (pintype "passive"))
      (node (ref "SV9") (pin "20") (pinfunction "20_20") (pintype "passive"))
    )
    (net (code "88") (name "Net-(SV10-Pad21)") (class "Default")
      (node (ref "SV10") (pin "21") (pinfunction "21_21") (pintype "passive"))
      (node (ref "SV9") (pin "21") (pinfunction "21_21") (pintype "passive"))
      (node (ref "SV9") (pin "22") (pinfunction "22_22") (pintype "passive"))
    )
    (net (code "89") (name "Net-(SV10-Pad23)") (class "Default")
      (node (ref "SV10") (pin "23") (pinfunction "23_23") (pintype "passive"))
      (node (ref "SV9") (pin "23") (pinfunction "23_23") (pintype "passive"))
      (node (ref "SV9") (pin "24") (pinfunction "24_24") (pintype "passive"))
    )
    (net (code "90") (name "Net-(SV10-Pad25)") (class "Default")
      (node (ref "SV10") (pin "25") (pinfunction "25_25") (pintype "passive"))
      (node (ref "SV9") (pin "25") (pinfunction "25_25") (pintype "passive"))
      (node (ref "SV9") (pin "26") (pinfunction "26_26") (pintype "passive"))
    )
    (net (code "91") (name "Net-(SV10-Pad27)") (class "Default")
      (node (ref "SV10") (pin "27") (pinfunction "27_27") (pintype "passive"))
      (node (ref "SV9") (pin "27") (pinfunction "27_27") (pintype "passive"))
      (node (ref "SV9") (pin "28") (pinfunction "28_28") (pintype "passive"))
    )
    (net (code "92") (name "Net-(SV10-Pad29)") (class "Default")
      (node (ref "SV10") (pin "29") (pinfunction "29_29") (pintype "passive"))
      (node (ref "SV9") (pin "29") (pinfunction "29_29") (pintype "passive"))
      (node (ref "SV9") (pin "30") (pinfunction "30_30") (pintype "passive"))
    )
    (net (code "93") (name "Net-(SV10-Pad31)") (class "Default")
      (node (ref "SV10") (pin "31") (pinfunction "31_31") (pintype "passive"))
      (node (ref "SV9") (pin "31") (pinfunction "31_31") (pintype "passive"))
      (node (ref "SV9") (pin "32") (pinfunction "32_32") (pintype "passive"))
    )
    (net (code "94") (name "Net-(SV10-Pad33)") (class "Default")
      (node (ref "SV10") (pin "33") (pinfunction "33_33") (pintype "passive"))
      (node (ref "SV9") (pin "33") (pinfunction "33_33") (pintype "passive"))
      (node (ref "SV9") (pin "34") (pinfunction "34_34") (pintype "passive"))
    )
    (net (code "95") (name "Net-(SV10-Pad35)") (class "Default")
      (node (ref "SV10") (pin "35") (pinfunction "35_35") (pintype "passive"))
      (node (ref "SV9") (pin "35") (pinfunction "35_35") (pintype "passive"))
      (node (ref "SV9") (pin "36") (pinfunction "36_36") (pintype "passive"))
    )
    (net (code "96") (name "Net-(SV11-Pad1)") (class "Default")
      (node (ref "SV11") (pin "1") (pinfunction "1_1") (pintype "passive"))
      (node (ref "SV11") (pin "2") (pinfunction "2_2") (pintype "passive"))
      (node (ref "SV12") (pin "1") (pinfunction "1_1") (pintype "passive"))
    )
    (net (code "97") (name "Net-(SV11-Pad3)") (class "Default")
      (node (ref "SV11") (pin "3") (pinfunction "3_3") (pintype "passive"))
      (node (ref "SV11") (pin "4") (pinfunction "4_4") (pintype "passive"))
      (node (ref "SV12") (pin "3") (pinfunction "3_3") (pintype "passive"))
    )
    (net (code "98") (name "Net-(SV11-Pad5)") (class "Default")
      (node (ref "SV11") (pin "5") (pinfunction "5_5") (pintype "passive"))
      (node (ref "SV11") (pin "6") (pinfunction "6_6") (pintype "passive"))
      (node (ref "SV12") (pin "5") (pinfunction "5_5") (pintype "passive"))
    )
    (net (code "99") (name "Net-(SV11-Pad7)") (class "Default")
      (node (ref "SV11") (pin "7") (pinfunction "7_7") (pintype "passive"))
      (node (ref "SV11") (pin "8") (pinfunction "8_8") (pintype "passive"))
      (node (ref "SV12") (pin "7") (pinfunction "7_7") (pintype "passive"))
    )
    (net (code "100") (name "Net-(SV11-Pad10)") (class "Default")
      (node (ref "SV11") (pin "10") (pinfunction "10_10") (pintype "passive"))
      (node (ref "SV11") (pin "9") (pinfunction "9_9") (pintype "passive"))
      (node (ref "SV12") (pin "9") (pinfunction "9_9") (pintype "passive"))
    )
    (net (code "101") (name "Net-(SV11-Pad11)") (class "Default")
      (node (ref "SV11") (pin "11") (pinfunction "11_11") (pintype "passive"))
      (node (ref "SV11") (pin "12") (pinfunction "12_12") (pintype "passive"))
      (node (ref "SV12") (pin "11") (pinfunction "11_11") (pintype "passive"))
    )
    (net (code "102") (name "Net-(SV11-Pad13)") (class "Default")
      (node (ref "SV11") (pin "13") (pinfunction "13_13") (pintype "passive"))
      (node (ref "SV11") (pin "14") (pinfunction "14_14") (pintype "passive"))
      (node (ref "SV12") (pin "13") (pinfunction "13_13") (pintype "passive"))
    )
    (net (code "103") (name "Net-(SV11-Pad15)") (class "Default")
      (node (ref "SV11") (pin "15") (pinfunction "15_15") (pintype "passive"))
      (node (ref "SV11") (pin "16") (pinfunction "16_16") (pintype "passive"))
      (node (ref "SV12") (pin "15") (pinfunction "15_15") (pintype "passive"))
    )
    (net (code "104") (name "Net-(SV11-Pad17)") (class "Default")
      (node (ref "SV11") (pin "17") (pinfunction "17_17") (pintype "passive"))
      (node (ref "SV11") (pin "18") (pinfunction "18_18") (pintype "passive"))
      (node (ref "SV12") (pin "17") (pinfunction "17_17") (pintype "passive"))
    )
    (net (code "105") (name "Net-(SV11-Pad19)") (class "Default")
      (node (ref "SV11") (pin "19") (pinfunction "19_19") (pintype "passive"))
      (node (ref "SV11") (pin "20") (pinfunction "20_20") (pintype "passive"))
      (node (ref "SV12") (pin "19") (pinfunction "19_19") (pintype "passive"))
    )
    (net (code "106") (name "Net-(SV11-Pad21)") (class "Default")
      (node (ref "SV11") (pin "21") (pinfunction "21_21") (pintype "passive"))
      (node (ref "SV11") (pin "22") (pinfunction "22_22") (pintype "passive"))
      (node (ref "SV12") (pin "21") (pinfunction "21_21") (pintype "passive"))
    )
    (net (code "107") (name "Net-(SV11-Pad23)") (class "Default")
      (node (ref "SV11") (pin "23") (pinfunction "23_23") (pintype "passive"))
      (node (ref "SV11") (pin "24") (pinfunction "24_24") (pintype "passive"))
      (node (ref "SV12") (pin "23") (pinfunction "23_23") (pintype "passive"))
    )
    (net (code "108") (name "Net-(SV11-Pad25)") (class "Default")
      (node (ref "SV11") (pin "25") (pinfunction "25_25") (pintype "passive"))
      (node (ref "SV11") (pin "26") (pinfunction "26_26") (pintype "passive"))
      (node (ref "SV12") (pin "25") (pinfunction "25_25") (pintype "passive"))
    )
    (net (code "109") (name "Net-(SV11-Pad27)") (class "Default")
      (node (ref "SV11") (pin "27") (pinfunction "27_27") (pintype "passive"))
      (node (ref "SV11") (pin "28") (pinfunction "28_28") (pintype "passive"))
      (node (ref "SV12") (pin "27") (pinfunction "27_27") (pintype "passive"))
    )
    (net (code "110") (name "Net-(SV11-Pad29)") (class "Default")
      (node (ref "SV11") (pin "29") (pinfunction "29_29") (pintype "passive"))
      (node (ref "SV11") (pin "30") (pinfunction "30_30") (pintype "passive"))
      (node (ref "SV12") (pin "29") (pinfunction "29_29") (pintype "passive"))
    )
    (net (code "111") (name "Net-(SV11-Pad31)") (class "Default")
      (node (ref "SV11") (pin "31") (pinfunction "31_31") (pintype "passive"))
      (node (ref "SV11") (pin "32") (pinfunction "32_32") (pintype "passive"))
      (node (ref "SV12") (pin "31") (pinfunction "31_31") (pintype "passive"))
    )
    (net (code "112") (name "Net-(SV11-Pad33)") (class "Default")
      (node (ref "SV11") (pin "33") (pinfunction "33_33") (pintype "passive"))
      (node (ref "SV11") (pin "34") (pinfunction "34_34") (pintype "passive"))
      (node (ref "SV12") (pin "33") (pinfunction "33_33") (pintype "passive"))
    )
    (net (code "113") (name "Net-(SV11-Pad35)") (class "Default")
      (node (ref "SV11") (pin "35") (pinfunction "35_35") (pintype "passive"))
      (node (ref "SV11") (pin "36") (pinfunction "36_36") (pintype "passive"))
      (node (ref "SV12") (pin "35") (pinfunction "35_35") (pintype "passive"))
    )
    (net (code "114") (name "Net-(SV11-Pad37)") (class "Default")
      (node (ref "SV11") (pin "37") (pinfunction "37_37") (pintype "passive"))
      (node (ref "SV11") (pin "38") (pinfunction "38_38") (pintype "passive"))
      (node (ref "SV12") (pin "37") (pinfunction "37_37") (pintype "passive"))
    )
    (net (code "115") (name "Net-(SV11-Pad39)") (class "Default")
      (node (ref "SV11") (pin "39") (pinfunction "39_39") (pintype "passive"))
      (node (ref "SV11") (pin "40") (pinfunction "40_40") (pintype "passive"))
      (node (ref "SV12") (pin "39") (pinfunction "39_39") (pintype "passive"))
    )
    (net (code "116") (name "Net-(SV13-Pad1)") (class "Default")
      (node (ref "SV13") (pin "1") (pinfunction "1_1") (pintype "passive"))
      (node (ref "SV13") (pin "2") (pinfunction "2_2") (pintype "passive"))
      (node (ref "SV14") (pin "2") (pinfunction "2_2") (pintype "passive"))
    )
    (net (code "117") (name "Net-(SV13-Pad3)") (class "Default")
      (node (ref "SV13") (pin "3") (pinfunction "3_3") (pintype "passive"))
      (node (ref "SV13") (pin "4") (pinfunction "4_4") (pintype "passive"))
      (node (ref "SV14") (pin "4") (pinfunction "4_4") (pintype "passive"))
    )
    (net (code "118") (name "Net-(SV13-Pad5)") (class "Default")
      (node (ref "SV13") (pin "5") (pinfunction "5_5") (pintype "passive"))
      (node (ref "SV13") (pin "6") (pinfunction "6_6") (pintype "passive"))
      (node (ref "SV14") (pin "6") (pinfunction "6_6") (pintype "passive"))
    )
    (net (code "119") (name "Net-(SV13-Pad7)") (class "Default")
      (node (ref "SV13") (pin "7") (pinfunction "7_7") (pintype "passive"))
      (node (ref "SV13") (pin "8") (pinfunction "8_8") (pintype "passive"))
      (node (ref "SV14") (pin "8") (pinfunction "8_8") (pintype "passive"))
    )
    (net (code "120") (name "Net-(SV13-Pad10)") (class "Default")
      (node (ref "SV13") (pin "10") (pinfunction "10_10") (pintype "passive"))
      (node (ref "SV13") (pin "9") (pinfunction "9_9") (pintype "passive"))
      (node (ref "SV14") (pin "10") (pinfunction "10_10") (pintype "passive"))
    )
    (net (code "121") (name "Net-(SV13-Pad11)") (class "Default")
      (node (ref "SV13") (pin "11") (pinfunction "11_11") (pintype "passive"))
      (node (ref "SV13") (pin "12") (pinfunction "12_12") (pintype "passive"))
      (node (ref "SV14") (pin "12") (pinfunction "12_12") (pintype "passive"))
    )
    (net (code "122") (name "Net-(SV13-Pad13)") (class "Default")
      (node (ref "SV13") (pin "13") (pinfunction "13_13") (pintype "passive"))
      (node (ref "SV13") (pin "14") (pinfunction "14_14") (pintype "passive"))
      (node (ref "SV14") (pin "14") (pinfunction "14_14") (pintype "passive"))
    )
    (net (code "123") (name "Net-(SV13-Pad15)") (class "Default")
      (node (ref "SV13") (pin "15") (pinfunction "15_15") (pintype "passive"))
      (node (ref "SV13") (pin "16") (pinfunction "16_16") (pintype "passive"))
      (node (ref "SV14") (pin "16") (pinfunction "16_16") (pintype "passive"))
    )
    (net (code "124") (name "Net-(SV13-Pad17)") (class "Default")
      (node (ref "SV13") (pin "17") (pinfunction "17_17") (pintype "passive"))
      (node (ref "SV13") (pin "18") (pinfunction "18_18") (pintype "passive"))
      (node (ref "SV14") (pin "18") (pinfunction "18_18") (pintype "passive"))
    )
    (net (code "125") (name "Net-(SV13-Pad19)") (class "Default")
      (node (ref "SV13") (pin "19") (pinfunction "19_19") (pintype "passive"))
      (node (ref "SV13") (pin "20") (pinfunction "20_20") (pintype "passive"))
      (node (ref "SV14") (pin "20") (pinfunction "20_20") (pintype "passive"))
    )
    (net (code "126") (name "Net-(SV13-Pad21)") (class "Default")
      (node (ref "SV13") (pin "21") (pinfunction "21_21") (pintype "passive"))
      (node (ref "SV13") (pin "22") (pinfunction "22_22") (pintype "passive"))
      (node (ref "SV14") (pin "22") (pinfunction "22_22") (pintype "passive"))
    )
    (net (code "127") (name "Net-(SV13-Pad23)") (class "Default")
      (node (ref "SV13") (pin "23") (pinfunction "23_23") (pintype "passive"))
      (node (ref "SV13") (pin "24") (pinfunction "24_24") (pintype "passive"))
      (node (ref "SV14") (pin "24") (pinfunction "24_24") (pintype "passive"))
    )
    (net (code "128") (name "Net-(SV13-Pad25)") (class "Default")
      (node (ref "SV13") (pin "25") (pinfunction "25_25") (pintype "passive"))
      (node (ref "SV13") (pin "26") (pinfunction "26_26") (pintype "passive"))
      (node (ref "SV14") (pin "26") (pinfunction "26_26") (pintype "passive"))
    )
    (net (code "129") (name "Net-(SV13-Pad27)") (class "Default")
      (node (ref "SV13") (pin "27") (pinfunction "27_27") (pintype "passive"))
      (node (ref "SV13") (pin "28") (pinfunction "28_28") (pintype "passive"))
      (node (ref "SV14") (pin "28") (pinfunction "28_28") (pintype "passive"))
    )
    (net (code "130") (name "Net-(SV13-Pad29)") (class "Default")
      (node (ref "SV13") (pin "29") (pinfunction "29_29") (pintype "passive"))
      (node (ref "SV13") (pin "30") (pinfunction "30_30") (pintype "passive"))
      (node (ref "SV14") (pin "30") (pinfunction "30_30") (pintype "passive"))
    )
    (net (code "131") (name "Net-(SV13-Pad31)") (class "Default")
      (node (ref "SV13") (pin "31") (pinfunction "31_31") (pintype "passive"))
      (node (ref "SV13") (pin "32") (pinfunction "32_32") (pintype "passive"))
      (node (ref "SV14") (pin "32") (pinfunction "32_32") (pintype "passive"))
    )
    (net (code "132") (name "Net-(SV13-Pad33)") (class "Default")
      (node (ref "SV13") (pin "33") (pinfunction "33_33") (pintype "passive"))
      (node (ref "SV13") (pin "34") (pinfunction "34_34") (pintype "passive"))
      (node (ref "SV14") (pin "34") (pinfunction "34_34") (pintype "passive"))
    )
    (net (code "133") (name "Net-(SV13-Pad35)") (class "Default")
      (node (ref "SV13") (pin "35") (pinfunction "35_35") (pintype "passive"))
      (node (ref "SV13") (pin "36") (pinfunction "36_36") (pintype "passive"))
      (node (ref "SV14") (pin "36") (pinfunction "36_36") (pintype "passive"))
    )
    (net (code "134") (name "Net-(SV13-Pad37)") (class "Default")
      (node (ref "SV13") (pin "37") (pinfunction "37_37") (pintype "passive"))
      (node (ref "SV13") (pin "38") (pinfunction "38_38") (pintype "passive"))
      (node (ref "SV14") (pin "38") (pinfunction "38_38") (pintype "passive"))
    )
    (net (code "135") (name "Net-(SV13-Pad39)") (class "Default")
      (node (ref "SV13") (pin "39") (pinfunction "39_39") (pintype "passive"))
      (node (ref "SV13") (pin "40") (pinfunction "40_40") (pintype "passive"))
      (node (ref "SV14") (pin "40") (pinfunction "40_40") (pintype "passive"))
    )
    (net (code "136") (name "Net-(SV15-Pad1)") (class "Default")
      (node (ref "SV15") (pin "1") (pinfunction "1_1") (pintype "passive"))
      (node (ref "SV15") (pin "2") (pinfunction "2_2") (pintype "passive"))
      (node (ref "SV16") (pin "2") (pinfunction "2_2") (pintype "passive"))
    )
    (net (code "137") (name "Net-(SV15-Pad3)") (class "Default")
      (node (ref "SV15") (pin "3") (pinfunction "3_3") (pintype "passive"))
      (node (ref "SV15") (pin "4") (pinfunction "4_4") (pintype "passive"))
      (node (ref "SV16") (pin "4") (pinfunction "4_4") (pintype "passive"))
    )
    (net (code "138") (name "Net-(SV15-Pad5)") (class "Default")
      (node (ref "SV15") (pin "5") (pinfunction "5_5") (pintype "passive"))
      (node (ref "SV15") (pin "6") (pinfunction "6_6") (pintype "passive"))
      (node (ref "SV16") (pin "6") (pinfunction "6_6") (pintype "passive"))
    )
    (net (code "139") (name "Net-(SV15-Pad7)") (class "Default")
      (node (ref "SV15") (pin "7") (pinfunction "7_7") (pintype "passive"))
      (node (ref "SV15") (pin "8") (pinfunction "8_8") (pintype "passive"))
      (node (ref "SV16") (pin "8") (pinfunction "8_8") (pintype "passive"))
    )
    (net (code "140") (name "Net-(SV15-Pad10)") (class "Default")
      (node (ref "SV15") (pin "10") (pinfunction "10_10") (pintype "passive"))
      (node (ref "SV15") (pin "9") (pinfunction "9_9") (pintype "passive"))
      (node (ref "SV16") (pin "10") (pinfunction "10_10") (pintype "passive"))
    )
    (net (code "141") (name "Net-(SV15-Pad11)") (class "Default")
      (node (ref "SV15") (pin "11") (pinfunction "11_11") (pintype "passive"))
      (node (ref "SV15") (pin "12") (pinfunction "12_12") (pintype "passive"))
      (node (ref "SV16") (pin "12") (pinfunction "12_12") (pintype "passive"))
    )
    (net (code "142") (name "Net-(SV15-Pad13)") (class "Default")
      (node (ref "SV15") (pin "13") (pinfunction "13_13") (pintype "passive"))
      (node (ref "SV15") (pin "14") (pinfunction "14_14") (pintype "passive"))
      (node (ref "SV16") (pin "14") (pinfunction "14_14") (pintype "passive"))
    )
    (net (code "143") (name "Net-(SV15-Pad15)") (class "Default")
      (node (ref "SV15") (pin "15") (pinfunction "15_15") (pintype "passive"))
      (node (ref "SV15") (pin "16") (pinfunction "16_16") (pintype "passive"))
      (node (ref "SV16") (pin "16") (pinfunction "16_16") (pintype "passive"))
    )
    (net (code "144") (name "Net-(SV15-Pad17)") (class "Default")
      (node (ref "SV15") (pin "17") (pinfunction "17_17") (pintype "passive"))
      (node (ref "SV15") (pin "18") (pinfunction "18_18") (pintype "passive"))
      (node (ref "SV16") (pin "18") (pinfunction "18_18") (pintype "passive"))
    )
    (net (code "145") (name "Net-(SV15-Pad19)") (class "Default")
      (node (ref "SV15") (pin "19") (pinfunction "19_19") (pintype "passive"))
      (node (ref "SV15") (pin "20") (pinfunction "20_20") (pintype "passive"))
      (node (ref "SV16") (pin "20") (pinfunction "20_20") (pintype "passive"))
    )
    (net (code "146") (name "Net-(SV15-Pad21)") (class "Default")
      (node (ref "SV15") (pin "21") (pinfunction "21_21") (pintype "passive"))
      (node (ref "SV15") (pin "22") (pinfunction "22_22") (pintype "passive"))
      (node (ref "SV16") (pin "22") (pinfunction "22_22") (pintype "passive"))
    )
    (net (code "147") (name "Net-(SV15-Pad23)") (class "Default")
      (node (ref "SV15") (pin "23") (pinfunction "23_23") (pintype "passive"))
      (node (ref "SV15") (pin "24") (pinfunction "24_24") (pintype "passive"))
      (node (ref "SV16") (pin "24") (pinfunction "24_24") (pintype "passive"))
    )
    (net (code "148") (name "Net-(SV15-Pad25)") (class "Default")
      (node (ref "SV15") (pin "25") (pinfunction "25_25") (pintype "passive"))
      (node (ref "SV15") (pin "26") (pinfunction "26_26") (pintype "passive"))
      (node (ref "SV16") (pin "26") (pinfunction "26_26") (pintype "passive"))
    )
    (net (code "149") (name "Net-(SV15-Pad27)") (class "Default")
      (node (ref "SV15") (pin "27") (pinfunction "27_27") (pintype "passive"))
      (node (ref "SV15") (pin "28") (pinfunction "28_28") (pintype "passive"))
      (node (ref "SV16") (pin "28") (pinfunction "28_28") (pintype "passive"))
    )
    (net (code "150") (name "Net-(SV15-Pad29)") (class "Default")
      (node (ref "SV15") (pin "29") (pinfunction "29_29") (pintype "passive"))
      (node (ref "SV15") (pin "30") (pinfunction "30_30") (pintype "passive"))
      (node (ref "SV16") (pin "30") (pinfunction "30_30") (pintype "passive"))
    )
    (net (code "151") (name "Net-(SV15-Pad31)") (class "Default")
      (node (ref "SV15") (pin "31") (pinfunction "31_31") (pintype "passive"))
      (node (ref "SV15") (pin "32") (pinfunction "32_32") (pintype "passive"))
      (node (ref "SV16") (pin "32") (pinfunction "32_32") (pintype "passive"))
    )
    (net (code "152") (name "Net-(SV15-Pad33)") (class "Default")
      (node (ref "SV15") (pin "33") (pinfunction "33_33") (pintype "passive"))
      (node (ref "SV15") (pin "34") (pinfunction "34_34") (pintype "passive"))
      (node (ref "SV16") (pin "34") (pinfunction "34_34") (pintype "passive"))
    )
    (net (code "153") (name "Net-(SV15-Pad35)") (class "Default")
      (node (ref "SV15") (pin "35") (pinfunction "35_35") (pintype "passive"))
      (node (ref "SV15") (pin "36") (pinfunction "36_36") (pintype "passive"))
      (node (ref "SV16") (pin "36") (pinfunction "36_36") (pintype "passive"))
    )
    (net (code "154") (name "Net-(SV17-Pad1)") (class "Default")
      (node (ref "SV17") (pin "1") (pinfunction "1_1") (pintype "passive"))
      (node (ref "SV17") (pin "2") (pinfunction "2_2") (pintype "passive"))
      (node (ref "SV18") (pin "1") (pinfunction "1_1") (pintype "passive"))
    )
    (net (code "155") (name "Net-(SV17-Pad3)") (class "Default")
      (node (ref "SV17") (pin "3") (pinfunction "3_3") (pintype "passive"))
      (node (ref "SV17") (pin "4") (pinfunction "4_4") (pintype "passive"))
      (node (ref "SV18") (pin "3") (pinfunction "3_3") (pintype "passive"))
    )
    (net (code "156") (name "Net-(SV17-Pad5)") (class "Default")
      (node (ref "SV17") (pin "5") (pinfunction "5_5") (pintype "passive"))
      (node (ref "SV17") (pin "6") (pinfunction "6_6") (pintype "passive"))
      (node (ref "SV18") (pin "5") (pinfunction "5_5") (pintype "passive"))
    )
    (net (code "157") (name "Net-(SV17-Pad7)") (class "Default")
      (node (ref "SV17") (pin "7") (pinfunction "7_7") (pintype "passive"))
      (node (ref "SV17") (pin "8") (pinfunction "8_8") (pintype "passive"))
      (node (ref "SV18") (pin "7") (pinfunction "7_7") (pintype "passive"))
    )
    (net (code "158") (name "Net-(SV17-Pad10)") (class "Default")
      (node (ref "SV17") (pin "10") (pinfunction "10_10") (pintype "passive"))
      (node (ref "SV17") (pin "9") (pinfunction "9_9") (pintype "passive"))
      (node (ref "SV18") (pin "9") (pinfunction "9_9") (pintype "passive"))
    )
    (net (code "159") (name "Net-(SV17-Pad11)") (class "Default")
      (node (ref "SV17") (pin "11") (pinfunction "11_11") (pintype "passive"))
      (node (ref "SV17") (pin "12") (pinfunction "12_12") (pintype "passive"))
      (node (ref "SV18") (pin "11") (pinfunction "11_11") (pintype "passive"))
    )
    (net (code "160") (name "Net-(SV17-Pad13)") (class "Default")
      (node (ref "SV17") (pin "13") (pinfunction "13_13") (pintype "passive"))
      (node (ref "SV17") (pin "14") (pinfunction "14_14") (pintype "passive"))
      (node (ref "SV18") (pin "13") (pinfunction "13_13") (pintype "passive"))
    )
    (net (code "161") (name "Net-(SV17-Pad15)") (class "Default")
      (node (ref "SV17") (pin "15") (pinfunction "15_15") (pintype "passive"))
      (node (ref "SV17") (pin "16") (pinfunction "16_16") (pintype "passive"))
      (node (ref "SV18") (pin "15") (pinfunction "15_15") (pintype "passive"))
    )
    (net (code "162") (name "Net-(SV17-Pad17)") (class "Default")
      (node (ref "SV17") (pin "17") (pinfunction "17_17") (pintype "passive"))
      (node (ref "SV17") (pin "18") (pinfunction "18_18") (pintype "passive"))
      (node (ref "SV18") (pin "17") (pinfunction "17_17") (pintype "passive"))
    )
    (net (code "163") (name "Net-(SV17-Pad19)") (class "Default")
      (node (ref "SV17") (pin "19") (pinfunction "19_19") (pintype "passive"))
      (node (ref "SV17") (pin "20") (pinfunction "20_20") (pintype "passive"))
      (node (ref "SV18") (pin "19") (pinfunction "19_19") (pintype "passive"))
    )
    (net (code "164") (name "Net-(SV17-Pad21)") (class "Default")
      (node (ref "SV17") (pin "21") (pinfunction "21_21") (pintype "passive"))
      (node (ref "SV17") (pin "22") (pinfunction "22_22") (pintype "passive"))
      (node (ref "SV18") (pin "21") (pinfunction "21_21") (pintype "passive"))
    )
    (net (code "165") (name "Net-(SV17-Pad23)") (class "Default")
      (node (ref "SV17") (pin "23") (pinfunction "23_23") (pintype "passive"))
      (node (ref "SV17") (pin "24") (pinfunction "24_24") (pintype "passive"))
      (node (ref "SV18") (pin "23") (pinfunction "23_23") (pintype "passive"))
    )
    (net (code "166") (name "Net-(SV17-Pad25)") (class "Default")
      (node (ref "SV17") (pin "25") (pinfunction "25_25") (pintype "passive"))
      (node (ref "SV17") (pin "26") (pinfunction "26_26") (pintype "passive"))
      (node (ref "SV18") (pin "25") (pinfunction "25_25") (pintype "passive"))
    )
    (net (code "167") (name "Net-(SV17-Pad27)") (class "Default")
      (node (ref "SV17") (pin "27") (pinfunction "27_27") (pintype "passive"))
      (node (ref "SV17") (pin "28") (pinfunction "28_28") (pintype "passive"))
      (node (ref "SV18") (pin "27") (pinfunction "27_27") (pintype "passive"))
    )
    (net (code "168") (name "Net-(SV17-Pad29)") (class "Default")
      (node (ref "SV17") (pin "29") (pinfunction "29_29") (pintype "passive"))
      (node (ref "SV17") (pin "30") (pinfunction "30_30") (pintype "passive"))
      (node (ref "SV18") (pin "29") (pinfunction "29_29") (pintype "passive"))
    )
    (net (code "169") (name "Net-(SV17-Pad31)") (class "Default")
      (node (ref "SV17") (pin "31") (pinfunction "31_31") (pintype "passive"))
      (node (ref "SV17") (pin "32") (pinfunction "32_32") (pintype "passive"))
      (node (ref "SV18") (pin "31") (pinfunction "31_31") (pintype "passive"))
    )
    (net (code "170") (name "Net-(SV17-Pad33)") (class "Default")
      (node (ref "SV17") (pin "33") (pinfunction "33_33") (pintype "passive"))
      (node (ref "SV17") (pin "34") (pinfunction "34_34") (pintype "passive"))
      (node (ref "SV18") (pin "33") (pinfunction "33_33") (pintype "passive"))
    )
    (net (code "171") (name "Net-(SV17-Pad35)") (class "Default")
      (node (ref "SV17") (pin "35") (pinfunction "35_35") (pintype "passive"))
      (node (ref "SV17") (pin "36") (pinfunction "36_36") (pintype "passive"))
      (node (ref "SV18") (pin "35") (pinfunction "35_35") (pintype "passive"))
    )
    (net (code "172") (name "Net-(SV19-Pad1)") (class "Default")
      (node (ref "SV19") (pin "1") (pinfunction "1_1") (pintype "passive"))
      (node (ref "SV19") (pin "2") (pinfunction "2_2") (pintype "passive"))
      (node (ref "SV20") (pin "1") (pinfunction "1_1") (pintype "passive"))
    )
    (net (code "173") (name "Net-(SV19-Pad3)") (class "Default")
      (node (ref "SV19") (pin "3") (pinfunction "3_3") (pintype "passive"))
      (node (ref "SV19") (pin "4") (pinfunction "4_4") (pintype "passive"))
      (node (ref "SV20") (pin "3") (pinfunction "3_3") (pintype "passive"))
    )
    (net (code "174") (name "Net-(SV19-Pad5)") (class "Default")
      (node (ref "SV19") (pin "5") (pinfunction "5_5") (pintype "passive"))
      (node (ref "SV19") (pin "6") (pinfunction "6_6") (pintype "passive"))
      (node (ref "SV20") (pin "5") (pinfunction "5_5") (pintype "passive"))
    )
    (net (code "175") (name "Net-(SV19-Pad7)") (class "Default")
      (node (ref "SV19") (pin "7") (pinfunction "7_7") (pintype "passive"))
      (node (ref "SV19") (pin "8") (pinfunction "8_8") (pintype "passive"))
      (node (ref "SV20") (pin "7") (pinfunction "7_7") (pintype "passive"))
    )
    (net (code "176") (name "Net-(SV19-Pad10)") (class "Default")
      (node (ref "SV19") (pin "10") (pinfunction "10_10") (pintype "passive"))
      (node (ref "SV19") (pin "9") (pinfunction "9_9") (pintype "passive"))
      (node (ref "SV20") (pin "9") (pinfunction "9_9") (pintype "passive"))
    )
    (net (code "177") (name "Net-(SV19-Pad11)") (class "Default")
      (node (ref "SV19") (pin "11") (pinfunction "11_11") (pintype "passive"))
      (node (ref "SV19") (pin "12") (pinfunction "12_12") (pintype "passive"))
      (node (ref "SV20") (pin "11") (pinfunction "11_11") (pintype "passive"))
    )
    (net (code "178") (name "Net-(SV19-Pad13)") (class "Default")
      (node (ref "SV19") (pin "13") (pinfunction "13_13") (pintype "passive"))
      (node (ref "SV19") (pin "14") (pinfunction "14_14") (pintype "passive"))
      (node (ref "SV20") (pin "13") (pinfunction "13_13") (pintype "passive"))
    )
    (net (code "179") (name "Net-(SV19-Pad15)") (class "Default")
      (node (ref "SV19") (pin "15") (pinfunction "15_15") (pintype "passive"))
      (node (ref "SV19") (pin "16") (pinfunction "16_16") (pintype "passive"))
      (node (ref "SV20") (pin "15") (pinfunction "15_15") (pintype "passive"))
    )
    (net (code "180") (name "Net-(SV19-Pad17)") (class "Default")
      (node (ref "SV19") (pin "17") (pinfunction "17_17") (pintype "passive"))
      (node (ref "SV19") (pin "18") (pinfunction "18_18") (pintype "passive"))
      (node (ref "SV20") (pin "17") (pinfunction "17_17") (pintype "passive"))
    )
    (net (code "181") (name "Net-(SV19-Pad19)") (class "Default")
      (node (ref "SV19") (pin "19") (pinfunction "19_19") (pintype "passive"))
      (node (ref "SV19") (pin "20") (pinfunction "20_20") (pintype "passive"))
      (node (ref "SV20") (pin "19") (pinfunction "19_19") (pintype "passive"))
    )
    (net (code "182") (name "Net-(SV19-Pad21)") (class "Default")
      (node (ref "SV19") (pin "21") (pinfunction "21_21") (pintype "passive"))
      (node (ref "SV19") (pin "22") (pinfunction "22_22") (pintype "passive"))
      (node (ref "SV20") (pin "21") (pinfunction "21_21") (pintype "passive"))
    )
    (net (code "183") (name "Net-(SV19-Pad23)") (class "Default")
      (node (ref "SV19") (pin "23") (pinfunction "23_23") (pintype "passive"))
      (node (ref "SV19") (pin "24") (pinfunction "24_24") (pintype "passive"))
      (node (ref "SV20") (pin "23") (pinfunction "23_23") (pintype "passive"))
    )
    (net (code "184") (name "Net-(SV19-Pad25)") (class "Default")
      (node (ref "SV19") (pin "25") (pinfunction "25_25") (pintype "passive"))
      (node (ref "SV19") (pin "26") (pinfunction "26_26") (pintype "passive"))
      (node (ref "SV20") (pin "25") (pinfunction "25_25") (pintype "passive"))
    )
    (net (code "185") (name "Net-(SV19-Pad27)") (class "Default")
      (node (ref "SV19") (pin "27") (pinfunction "27_27") (pintype "passive"))
      (node (ref "SV19") (pin "28") (pinfunction "28_28") (pintype "passive"))
      (node (ref "SV20") (pin "27") (pinfunction "27_27") (pintype "passive"))
    )
    (net (code "186") (name "Net-(SV19-Pad29)") (class "Default")
      (node (ref "SV19") (pin "29") (pinfunction "29_29") (pintype "passive"))
      (node (ref "SV19") (pin "30") (pinfunction "30_30") (pintype "passive"))
      (node (ref "SV20") (pin "29") (pinfunction "29_29") (pintype "passive"))
    )
    (net (code "187") (name "Net-(SV19-Pad31)") (class "Default")
      (node (ref "SV19") (pin "31") (pinfunction "31_31") (pintype "passive"))
      (node (ref "SV19") (pin "32") (pinfunction "32_32") (pintype "passive"))
      (node (ref "SV20") (pin "31") (pinfunction "31_31") (pintype "passive"))
    )
    (net (code "188") (name "Net-(SV19-Pad33)") (class "Default")
      (node (ref "SV19") (pin "33") (pinfunction "33_33") (pintype "passive"))
      (node (ref "SV19") (pin "34") (pinfunction "34_34") (pintype "passive"))
      (node (ref "SV20") (pin "33") (pinfunction "33_33") (pintype "passive"))
    )
    (net (code "189") (name "Net-(SV19-Pad35)") (class "Default")
      (node (ref "SV19") (pin "35") (pinfunction "35_35") (pintype "passive"))
      (node (ref "SV19") (pin "36") (pinfunction "36_36") (pintype "passive"))
      (node (ref "SV20") (pin "35") (pinfunction "35_35") (pintype "passive"))
    )
    (net (code "190") (name "Net-(SV19-Pad37)") (class "Default")
      (node (ref "SV19") (pin "37") (pinfunction "37_37") (pintype "passive"))
      (node (ref "SV19") (pin "38") (pinfunction "38_38") (pintype "passive"))
      (node (ref "SV20") (pin "37") (pinfunction "37_37") (pintype "passive"))
    )
    (net (code "191") (name "Net-(SV19-Pad39)") (class "Default")
      (node (ref "SV19") (pin "39") (pinfunction "39_39") (pintype "passive"))
      (node (ref "SV19") (pin "40") (pinfunction "40_40") (pintype "passive"))
      (node (ref "SV20") (pin "39") (pinfunction "39_39") (pintype "passive"))
    )
    (net (code "192") (name "Net-(SV21-Pad1)") (class "Default")
      (node (ref "SV21") (pin "1") (pinfunction "1_1") (pintype "passive"))
      (node (ref "SV21") (pin "2") (pinfunction "2_2") (pintype "passive"))
      (node (ref "SV22") (pin "2") (pinfunction "2_2") (pintype "passive"))
    )
    (net (code "193") (name "Net-(SV21-Pad3)") (class "Default")
      (node (ref "SV21") (pin "3") (pinfunction "3_3") (pintype "passive"))
      (node (ref "SV21") (pin "4") (pinfunction "4_4") (pintype "passive"))
      (node (ref "SV22") (pin "4") (pinfunction "4_4") (pintype "passive"))
    )
    (net (code "194") (name "Net-(SV21-Pad5)") (class "Default")
      (node (ref "SV21") (pin "5") (pinfunction "5_5") (pintype "passive"))
      (node (ref "SV21") (pin "6") (pinfunction "6_6") (pintype "passive"))
      (node (ref "SV22") (pin "6") (pinfunction "6_6") (pintype "passive"))
    )
    (net (code "195") (name "Net-(SV21-Pad7)") (class "Default")
      (node (ref "SV21") (pin "7") (pinfunction "7_7") (pintype "passive"))
      (node (ref "SV21") (pin "8") (pinfunction "8_8") (pintype "passive"))
      (node (ref "SV22") (pin "8") (pinfunction "8_8") (pintype "passive"))
    )
    (net (code "196") (name "Net-(SV21-Pad10)") (class "Default")
      (node (ref "SV21") (pin "10") (pinfunction "10_10") (pintype "passive"))
      (node (ref "SV21") (pin "9") (pinfunction "9_9") (pintype "passive"))
      (node (ref "SV22") (pin "10") (pinfunction "10_10") (pintype "passive"))
    )
    (net (code "197") (name "Net-(SV21-Pad11)") (class "Default")
      (node (ref "SV21") (pin "11") (pinfunction "11_11") (pintype "passive"))
      (node (ref "SV21") (pin "12") (pinfunction "12_12") (pintype "passive"))
      (node (ref "SV22") (pin "12") (pinfunction "12_12") (pintype "passive"))
    )
    (net (code "198") (name "Net-(SV21-Pad13)") (class "Default")
      (node (ref "SV21") (pin "13") (pinfunction "13_13") (pintype "passive"))
      (node (ref "SV21") (pin "14") (pinfunction "14_14") (pintype "passive"))
      (node (ref "SV22") (pin "14") (pinfunction "14_14") (pintype "passive"))
    )
    (net (code "199") (name "Net-(SV21-Pad15)") (class "Default")
      (node (ref "SV21") (pin "15") (pinfunction "15_15") (pintype "passive"))
      (node (ref "SV21") (pin "16") (pinfunction "16_16") (pintype "passive"))
      (node (ref "SV22") (pin "16") (pinfunction "16_16") (pintype "passive"))
    )
    (net (code "200") (name "Net-(SV21-Pad17)") (class "Default")
      (node (ref "SV21") (pin "17") (pinfunction "17_17") (pintype "passive"))
      (node (ref "SV21") (pin "18") (pinfunction "18_18") (pintype "passive"))
      (node (ref "SV22") (pin "18") (pinfunction "18_18") (pintype "passive"))
    )
    (net (code "201") (name "Net-(SV21-Pad19)") (class "Default")
      (node (ref "SV21") (pin "19") (pinfunction "19_19") (pintype "passive"))
      (node (ref "SV21") (pin "20") (pinfunction "20_20") (pintype "passive"))
      (node (ref "SV22") (pin "20") (pinfunction "20_20") (pintype "passive"))
    )
    (net (code "202") (name "Net-(SV21-Pad21)") (class "Default")
      (node (ref "SV21") (pin "21") (pinfunction "21_21") (pintype "passive"))
      (node (ref "SV21") (pin "22") (pinfunction "22_22") (pintype "passive"))
      (node (ref "SV22") (pin "22") (pinfunction "22_22") (pintype "passive"))
    )
    (net (code "203") (name "Net-(SV21-Pad23)") (class "Default")
      (node (ref "SV21") (pin "23") (pinfunction "23_23") (pintype "passive"))
      (node (ref "SV21") (pin "24") (pinfunction "24_24") (pintype "passive"))
      (node (ref "SV22") (pin "24") (pinfunction "24_24") (pintype "passive"))
    )
    (net (code "204") (name "Net-(SV21-Pad25)") (class "Default")
      (node (ref "SV21") (pin "25") (pinfunction "25_25") (pintype "passive"))
      (node (ref "SV21") (pin "26") (pinfunction "26_26") (pintype "passive"))
      (node (ref "SV22") (pin "26") (pinfunction "26_26") (pintype "passive"))
    )
    (net (code "205") (name "Net-(SV21-Pad27)") (class "Default")
      (node (ref "SV21") (pin "27") (pinfunction "27_27") (pintype "passive"))
      (node (ref "SV21") (pin "28") (pinfunction "28_28") (pintype "passive"))
      (node (ref "SV22") (pin "28") (pinfunction "28_28") (pintype "passive"))
    )
    (net (code "206") (name "Net-(SV21-Pad29)") (class "Default")
      (node (ref "SV21") (pin "29") (pinfunction "29_29") (pintype "passive"))
      (node (ref "SV21") (pin "30") (pinfunction "30_30") (pintype "passive"))
      (node (ref "SV22") (pin "30") (pinfunction "30_30") (pintype "passive"))
    )
    (net (code "207") (name "Net-(SV21-Pad31)") (class "Default")
      (node (ref "SV21") (pin "31") (pinfunction "31_31") (pintype "passive"))
      (node (ref "SV21") (pin "32") (pinfunction "32_32") (pintype "passive"))
      (node (ref "SV22") (pin "32") (pinfunction "32_32") (pintype "passive"))
    )
    (net (code "208") (name "Net-(SV21-Pad33)") (class "Default")
      (node (ref "SV21") (pin "33") (pinfunction "33_33") (pintype "passive"))
      (node (ref "SV21") (pin "34") (pinfunction "34_34") (pintype "passive"))
      (node (ref "SV22") (pin "34") (pinfunction "34_34") (pintype "passive"))
    )
    (net (code "209") (name "Net-(SV21-Pad35)") (class "Default")
      (node (ref "SV21") (pin "35") (pinfunction "35_35") (pintype "passive"))
      (node (ref "SV21") (pin "36") (pinfunction "36_36") (pintype "passive"))
      (node (ref "SV22") (pin "36") (pinfunction "36_36") (pintype "passive"))
    )
    (net (code "210") (name "Net-(SV21-Pad37)") (class "Default")
      (node (ref "SV21") (pin "37") (pinfunction "37_37") (pintype "passive"))
      (node (ref "SV21") (pin "38") (pinfunction "38_38") (pintype "passive"))
      (node (ref "SV22") (pin "38") (pinfunction "38_38") (pintype "passive"))
    )
    (net (code "211") (name "Net-(SV21-Pad39)") (class "Default")
      (node (ref "SV21") (pin "39") (pinfunction "39_39") (pintype "passive"))
      (node (ref "SV21") (pin "40") (pinfunction "40_40") (pintype "passive"))
      (node (ref "SV22") (pin "40") (pinfunction "40_40") (pintype "passive"))
    )
    (net (code "212") (name "Net-(SV23-Pad1)") (class "Default")
      (node (ref "SV23") (pin "1") (pinfunction "1_1") (pintype "passive"))
      (node (ref "SV23") (pin "2") (pinfunction "2_2") (pintype "passive"))
      (node (ref "SV24") (pin "2") (pinfunction "2_2") (pintype "passive"))
    )
    (net (code "213") (name "Net-(SV23-Pad3)") (class "Default")
      (node (ref "SV23") (pin "3") (pinfunction "3_3") (pintype "passive"))
      (node (ref "SV23") (pin "4") (pinfunction "4_4") (pintype "passive"))
      (node (ref "SV24") (pin "4") (pinfunction "4_4") (pintype "passive"))
    )
    (net (code "214") (name "Net-(SV23-Pad5)") (class "Default")
      (node (ref "SV23") (pin "5") (pinfunction "5_5") (pintype "passive"))
      (node (ref "SV23") (pin "6") (pinfunction "6_6") (pintype "passive"))
      (node (ref "SV24") (pin "6") (pinfunction "6_6") (pintype "passive"))
    )
    (net (code "215") (name "Net-(SV23-Pad7)") (class "Default")
      (node (ref "SV23") (pin "7") (pinfunction "7_7") (pintype "passive"))
      (node (ref "SV23") (pin "8") (pinfunction "8_8") (pintype "passive"))
      (node (ref "SV24") (pin "8") (pinfunction "8_8") (pintype "passive"))
    )
    (net (code "216") (name "Net-(SV23-Pad10)") (class "Default")
      (node (ref "SV23") (pin "10") (pinfunction "10_10") (pintype "passive"))
      (node (ref "SV23") (pin "9") (pinfunction "9_9") (pintype "passive"))
      (node (ref "SV24") (pin "10") (pinfunction "10_10") (pintype "passive"))
    )
    (net (code "217") (name "Net-(SV23-Pad11)") (class "Default")
      (node (ref "SV23") (pin "11") (pinfunction "11_11") (pintype "passive"))
      (node (ref "SV23") (pin "12") (pinfunction "12_12") (pintype "passive"))
      (node (ref "SV24") (pin "12") (pinfunction "12_12") (pintype "passive"))
    )
    (net (code "218") (name "Net-(SV23-Pad13)") (class "Default")
      (node (ref "SV23") (pin "13") (pinfunction "13_13") (pintype "passive"))
      (node (ref "SV23") (pin "14") (pinfunction "14_14") (pintype "passive"))
      (node (ref "SV24") (pin "14") (pinfunction "14_14") (pintype "passive"))
    )
    (net (code "219") (name "Net-(SV23-Pad15)") (class "Default")
      (node (ref "SV23") (pin "15") (pinfunction "15_15") (pintype "passive"))
      (node (ref "SV23") (pin "16") (pinfunction "16_16") (pintype "passive"))
      (node (ref "SV24") (pin "16") (pinfunction "16_16") (pintype "passive"))
    )
    (net (code "220") (name "Net-(SV23-Pad17)") (class "Default")
      (node (ref "SV23") (pin "17") (pinfunction "17_17") (pintype "passive"))
      (node (ref "SV23") (pin "18") (pinfunction "18_18") (pintype "passive"))
      (node (ref "SV24") (pin "18") (pinfunction "18_18") (pintype "passive"))
    )
    (net (code "221") (name "Net-(SV23-Pad19)") (class "Default")
      (node (ref "SV23") (pin "19") (pinfunction "19_19") (pintype "passive"))
      (node (ref "SV23") (pin "20") (pinfunction "20_20") (pintype "passive"))
      (node (ref "SV24") (pin "20") (pinfunction "20_20") (pintype "passive"))
    )
    (net (code "222") (name "Net-(SV23-Pad21)") (class "Default")
      (node (ref "SV23") (pin "21") (pinfunction "21_21") (pintype "passive"))
      (node (ref "SV23") (pin "22") (pinfunction "22_22") (pintype "passive"))
      (node (ref "SV24") (pin "22") (pinfunction "22_22") (pintype "passive"))
    )
    (net (code "223") (name "Net-(SV23-Pad23)") (class "Default")
      (node (ref "SV23") (pin "23") (pinfunction "23_23") (pintype "passive"))
      (node (ref "SV23") (pin "24") (pinfunction "24_24") (pintype "passive"))
      (node (ref "SV24") (pin "24") (pinfunction "24_24") (pintype "passive"))
    )
    (net (code "224") (name "Net-(SV23-Pad25)") (class "Default")
      (node (ref "SV23") (pin "25") (pinfunction "25_25") (pintype "passive"))
      (node (ref "SV23") (pin "26") (pinfunction "26_26") (pintype "passive"))
      (node (ref "SV24") (pin "26") (pinfunction "26_26") (pintype "passive"))
    )
    (net (code "225") (name "Net-(SV23-Pad27)") (class "Default")
      (node (ref "SV23") (pin "27") (pinfunction "27_27") (pintype "passive"))
      (node (ref "SV23") (pin "28") (pinfunction "28_28") (pintype "passive"))
      (node (ref "SV24") (pin "28") (pinfunction "28_28") (pintype "passive"))
    )
    (net (code "226") (name "Net-(SV23-Pad29)") (class "Default")
      (node (ref "SV23") (pin "29") (pinfunction "29_29") (pintype "passive"))
      (node (ref "SV23") (pin "30") (pinfunction "30_30") (pintype "passive"))
      (node (ref "SV24") (pin "30") (pinfunction "30_30") (pintype "passive"))
    )
    (net (code "227") (name "Net-(SV23-Pad31)") (class "Default")
      (node (ref "SV23") (pin "31") (pinfunction "31_31") (pintype "passive"))
      (node (ref "SV23") (pin "32") (pinfunction "32_32") (pintype "passive"))
      (node (ref "SV24") (pin "32") (pinfunction "32_32") (pintype "passive"))
    )
    (net (code "228") (name "Net-(SV23-Pad33)") (class "Default")
      (node (ref "SV23") (pin "33") (pinfunction "33_33") (pintype "passive"))
      (node (ref "SV23") (pin "34") (pinfunction "34_34") (pintype "passive"))
      (node (ref "SV24") (pin "34") (pinfunction "34_34") (pintype "passive"))
    )
    (net (code "229") (name "Net-(SV23-Pad35)") (class "Default")
      (node (ref "SV23") (pin "35") (pinfunction "35_35") (pintype "passive"))
      (node (ref "SV23") (pin "36") (pinfunction "36_36") (pintype "passive"))
      (node (ref "SV24") (pin "36") (pinfunction "36_36") (pintype "passive"))
    )
    (net (code "230") (name "Net-(U$1A-1)") (class "Default")
      (node (ref "U$1") (pin "A1") (pinfunction "1_A1") (pintype "bidirectional"))
      (node (ref "U$3") (pin "A1") (pinfunction "P$1_A1") (pintype "passive"))
    )
    (net (code "231") (name "Net-(U$1AA-1)") (class "Default")
      (node (ref "U$1") (pin "R1") (pinfunction "1_R1") (pintype "bidirectional"))
      (node (ref "U$3") (pin "R1") (pinfunction "P$1_R1") (pintype "passive"))
    )
    (net (code "232") (name "Net-(U$1AB-1)") (class "Default")
      (node (ref "U$1") (pin "R2") (pinfunction "1_R2") (pintype "bidirectional"))
      (node (ref "U$3") (pin "R2") (pinfunction "P$1_R2") (pintype "passive"))
    )
    (net (code "233") (name "Net-(U$1AC-1)") (class "Default")
      (node (ref "U$1") (pin "S1") (pinfunction "1_S1") (pintype "bidirectional"))
      (node (ref "U$3") (pin "S1") (pinfunction "P$1_S1") (pintype "passive"))
    )
    (net (code "234") (name "Net-(U$1AD-1)") (class "Default")
      (node (ref "U$1") (pin "S2") (pinfunction "1_S2") (pintype "bidirectional"))
      (node (ref "U$3") (pin "S2") (pinfunction "P$1_S2") (pintype "passive"))
    )
    (net (code "235") (name "Net-(U$1AE-1)") (class "Default")
      (node (ref "U$1") (pin "T1") (pinfunction "1_T1") (pintype "bidirectional"))
      (node (ref "U$3") (pin "T1") (pinfunction "P$1_T1") (pintype "passive"))
    )
    (net (code "236") (name "Net-(U$1AF-1)") (class "Default")
      (node (ref "U$1") (pin "T2") (pinfunction "1_T2") (pintype "bidirectional"))
      (node (ref "U$3") (pin "T2") (pinfunction "P$1_T2") (pintype "passive"))
    )
    (net (code "237") (name "Net-(U$1AG-1)") (class "Default")
      (node (ref "U$1") (pin "U1") (pinfunction "1_U1") (pintype "bidirectional"))
      (node (ref "U$3") (pin "U1") (pinfunction "P$1_U1") (pintype "passive"))
    )
    (net (code "238") (name "Net-(U$1AH-1)") (class "Default")
      (node (ref "U$1") (pin "U2") (pinfunction "1_U2") (pintype "bidirectional"))
      (node (ref "U$3") (pin "U2") (pinfunction "P$1_U2") (pintype "passive"))
    )
    (net (code "239") (name "Net-(U$1AI-1)") (class "Default")
      (node (ref "U$1") (pin "V1") (pinfunction "1_V1") (pintype "bidirectional"))
      (node (ref "U$3") (pin "V1") (pinfunction "P$1_V1") (pintype "passive"))
    )
    (net (code "240") (name "Net-(U$1AJ-1)") (class "Default")
      (node (ref "U$1") (pin "V2") (pinfunction "1_V2") (pintype "bidirectional"))
      (node (ref "U$3") (pin "V2") (pinfunction "P$1_V2") (pintype "passive"))
    )
    (net (code "241") (name "Net-(U$1C-1)") (class "Default")
      (node (ref "U$1") (pin "B1") (pinfunction "1_B1") (pintype "bidirectional"))
      (node (ref "U$3") (pin "B1") (pinfunction "P$1_B1") (pintype "passive"))
    )
    (net (code "242") (name "Net-(U$1D-1)") (class "Default")
      (node (ref "U$1") (pin "B2") (pinfunction "1_B2") (pintype "bidirectional"))
      (node (ref "U$3") (pin "B2") (pinfunction "P$1_B2") (pintype "passive"))
    )
    (net (code "243") (name "Net-(U$1E-1)") (class "Default")
      (node (ref "U$1") (pin "C1") (pinfunction "1_C1") (pintype "bidirectional"))
      (node (ref "U$3") (pin "C1") (pinfunction "P$1_C1") (pintype "passive"))
    )
    (net (code "244") (name "Net-(U$1G-1)") (class "Default")
      (node (ref "U$1") (pin "D1") (pinfunction "1_D1") (pintype "bidirectional"))
      (node (ref "U$3") (pin "D1") (pinfunction "P$1_D1") (pintype "passive"))
    )
    (net (code "245") (name "Net-(U$1H-1)") (class "Default")
      (node (ref "U$1") (pin "D2") (pinfunction "1_D2") (pintype "bidirectional"))
      (node (ref "U$3") (pin "D2") (pinfunction "P$1_D2") (pintype "passive"))
    )
    (net (code "246") (name "Net-(U$1I-1)") (class "Default")
      (node (ref "U$1") (pin "E1") (pinfunction "1_E1") (pintype "bidirectional"))
      (node (ref "U$3") (pin "E1") (pinfunction "P$1_E1") (pintype "passive"))
    )
    (net (code "247") (name "Net-(U$1J-1)") (class "Default")
      (node (ref "U$1") (pin "E2") (pinfunction "1_E2") (pintype "bidirectional"))
      (node (ref "U$3") (pin "E2") (pinfunction "P$1_E2") (pintype "passive"))
    )
    (net (code "248") (name "Net-(U$1K-1)") (class "Default")
      (node (ref "U$1") (pin "F1") (pinfunction "1_F1") (pintype "bidirectional"))
      (node (ref "U$3") (pin "F1") (pinfunction "P$1_F1") (pintype "passive"))
    )
    (net (code "249") (name "Net-(U$1L-1)") (class "Default")
      (node (ref "U$1") (pin "F2") (pinfunction "1_F2") (pintype "bidirectional"))
      (node (ref "U$3") (pin "F2") (pinfunction "P$1_F2") (pintype "passive"))
    )
    (net (code "250") (name "Net-(U$1M-1)") (class "Default")
      (node (ref "U$1") (pin "H1") (pinfunction "1_H1") (pintype "bidirectional"))
      (node (ref "U$3") (pin "H1") (pinfunction "P$1_H1") (pintype "passive"))
    )
    (net (code "251") (name "Net-(U$1N-1)") (class "Default")
      (node (ref "U$1") (pin "H2") (pinfunction "1_H2") (pintype "bidirectional"))
      (node (ref "U$3") (pin "H2") (pinfunction "P$1_H2") (pintype "passive"))
    )
    (net (code "252") (name "Net-(U$1O-1)") (class "Default")
      (node (ref "U$1") (pin "J1") (pinfunction "1_J1") (pintype "bidirectional"))
      (node (ref "U$3") (pin "J1") (pinfunction "P$1_J1") (pintype "passive"))
    )
    (net (code "253") (name "Net-(U$1P-1)") (class "Default")
      (node (ref "U$1") (pin "J2") (pinfunction "1_J2") (pintype "bidirectional"))
      (node (ref "U$3") (pin "J2") (pinfunction "P$1_J2") (pintype "passive"))
    )
    (net (code "254") (name "Net-(U$1Q-1)") (class "Default")
      (node (ref "U$1") (pin "K1") (pinfunction "1_K1") (pintype "bidirectional"))
      (node (ref "U$3") (pin "K1") (pinfunction "P$1_K1") (pintype "passive"))
    )
    (net (code "255") (name "Net-(U$1R-1)") (class "Default")
      (node (ref "U$1") (pin "K2") (pinfunction "1_K2") (pintype "bidirectional"))
      (node (ref "U$3") (pin "K2") (pinfunction "P$1_K2") (pintype "passive"))
    )
    (net (code "256") (name "Net-(U$1S-1)") (class "Default")
      (node (ref "U$1") (pin "L1") (pinfunction "1_L1") (pintype "bidirectional"))
      (node (ref "U$3") (pin "L1") (pinfunction "P$1_L1") (pintype "passive"))
    )
    (net (code "257") (name "Net-(U$1T-1)") (class "Default")
      (node (ref "U$1") (pin "L2") (pinfunction "1_L2") (pintype "bidirectional"))
      (node (ref "U$3") (pin "L2") (pinfunction "P$1_L2") (pintype "passive"))
    )
    (net (code "258") (name "Net-(U$1U-1)") (class "Default")
      (node (ref "U$1") (pin "M1") (pinfunction "1_M1") (pintype "bidirectional"))
      (node (ref "U$3") (pin "M1") (pinfunction "P$1_M1") (pintype "passive"))
    )
    (net (code "259") (name "Net-(U$1V-1)") (class "Default")
      (node (ref "U$1") (pin "M2") (pinfunction "1_M2") (pintype "bidirectional"))
      (node (ref "U$3") (pin "M2") (pinfunction "P$1_M2") (pintype "passive"))
    )
    (net (code "260") (name "Net-(U$1W-1)") (class "Default")
      (node (ref "U$1") (pin "N1") (pinfunction "1_N1") (pintype "bidirectional"))
      (node (ref "U$3") (pin "N1") (pinfunction "P$1_N1") (pintype "passive"))
    )
    (net (code "261") (name "Net-(U$1X-1)") (class "Default")
      (node (ref "U$1") (pin "N2") (pinfunction "1_N2") (pintype "bidirectional"))
      (node (ref "U$3") (pin "N2") (pinfunction "P$1_N2") (pintype "passive"))
    )
    (net (code "262") (name "Net-(U$1Y-1)") (class "Default")
      (node (ref "U$1") (pin "P1") (pinfunction "1_P1") (pintype "bidirectional"))
      (node (ref "U$3") (pin "P1") (pinfunction "P$1_P1") (pintype "passive"))
    )
    (net (code "263") (name "Net-(U$1Z-1)") (class "Default")
      (node (ref "U$1") (pin "P2") (pinfunction "1_P2") (pintype "bidirectional"))
      (node (ref "U$3") (pin "P2") (pinfunction "P$1_P2") (pintype "passive"))
    )
    (net (code "264") (name "VCC") (class "Default")
      (node (ref "SV10") (pin "10") (pinfunction "10_10") (pintype "passive"))
      (node (ref "SV10") (pin "12") (pinfunction "12_12") (pintype "passive"))
      (node (ref "SV10") (pin "14") (pinfunction "14_14") (pintype "passive"))
      (node (ref "SV10") (pin "16") (pinfunction "16_16") (pintype "passive"))
      (node (ref "SV10") (pin "18") (pinfunction "18_18") (pintype "passive"))
      (node (ref "SV10") (pin "2") (pinfunction "2_2") (pintype "passive"))
      (node (ref "SV10") (pin "20") (pinfunction "20_20") (pintype "passive"))
      (node (ref "SV10") (pin "22") (pinfunction "22_22") (pintype "passive"))
      (node (ref "SV10") (pin "24") (pinfunction "24_24") (pintype "passive"))
      (node (ref "SV10") (pin "26") (pinfunction "26_26") (pintype "passive"))
      (node (ref "SV10") (pin "28") (pinfunction "28_28") (pintype "passive"))
      (node (ref "SV10") (pin "30") (pinfunction "30_30") (pintype "passive"))
      (node (ref "SV10") (pin "32") (pinfunction "32_32") (pintype "passive"))
      (node (ref "SV10") (pin "34") (pinfunction "34_34") (pintype "passive"))
      (node (ref "SV10") (pin "36") (pinfunction "36_36") (pintype "passive"))
      (node (ref "SV10") (pin "4") (pinfunction "4_4") (pintype "passive"))
      (node (ref "SV10") (pin "6") (pinfunction "6_6") (pintype "passive"))
      (node (ref "SV10") (pin "8") (pinfunction "8_8") (pintype "passive"))
      (node (ref "SV12") (pin "10") (pinfunction "10_10") (pintype "passive"))
      (node (ref "SV12") (pin "12") (pinfunction "12_12") (pintype "passive"))
      (node (ref "SV12") (pin "14") (pinfunction "14_14") (pintype "passive"))
      (node (ref "SV12") (pin "16") (pinfunction "16_16") (pintype "passive"))
      (node (ref "SV12") (pin "18") (pinfunction "18_18") (pintype "passive"))
      (node (ref "SV12") (pin "2") (pinfunction "2_2") (pintype "passive"))
      (node (ref "SV12") (pin "20") (pinfunction "20_20") (pintype "passive"))
      (node (ref "SV12") (pin "22") (pinfunction "22_22") (pintype "passive"))
      (node (ref "SV12") (pin "24") (pinfunction "24_24") (pintype "passive"))
      (node (ref "SV12") (pin "26") (pinfunction "26_26") (pintype "passive"))
      (node (ref "SV12") (pin "28") (pinfunction "28_28") (pintype "passive"))
      (node (ref "SV12") (pin "30") (pinfunction "30_30") (pintype "passive"))
      (node (ref "SV12") (pin "32") (pinfunction "32_32") (pintype "passive"))
      (node (ref "SV12") (pin "34") (pinfunction "34_34") (pintype "passive"))
      (node (ref "SV12") (pin "36") (pinfunction "36_36") (pintype "passive"))
      (node (ref "SV12") (pin "38") (pinfunction "38_38") (pintype "passive"))
      (node (ref "SV12") (pin "4") (pinfunction "4_4") (pintype "passive"))
      (node (ref "SV12") (pin "40") (pinfunction "40_40") (pintype "passive"))
      (node (ref "SV12") (pin "6") (pinfunction "6_6") (pintype "passive"))
      (node (ref "SV12") (pin "8") (pinfunction "8_8") (pintype "passive"))
      (node (ref "SV18") (pin "10") (pinfunction "10_10") (pintype "passive"))
      (node (ref "SV18") (pin "12") (pinfunction "12_12") (pintype "passive"))
      (node (ref "SV18") (pin "14") (pinfunction "14_14") (pintype "passive"))
      (node (ref "SV18") (pin "16") (pinfunction "16_16") (pintype "passive"))
      (node (ref "SV18") (pin "18") (pinfunction "18_18") (pintype "passive"))
      (node (ref "SV18") (pin "2") (pinfunction "2_2") (pintype "passive"))
      (node (ref "SV18") (pin "20") (pinfunction "20_20") (pintype "passive"))
      (node (ref "SV18") (pin "22") (pinfunction "22_22") (pintype "passive"))
      (node (ref "SV18") (pin "24") (pinfunction "24_24") (pintype "passive"))
      (node (ref "SV18") (pin "26") (pinfunction "26_26") (pintype "passive"))
      (node (ref "SV18") (pin "28") (pinfunction "28_28") (pintype "passive"))
      (node (ref "SV18") (pin "30") (pinfunction "30_30") (pintype "passive"))
      (node (ref "SV18") (pin "32") (pinfunction "32_32") (pintype "passive"))
      (node (ref "SV18") (pin "34") (pinfunction "34_34") (pintype "passive"))
      (node (ref "SV18") (pin "36") (pinfunction "36_36") (pintype "passive"))
      (node (ref "SV18") (pin "4") (pinfunction "4_4") (pintype "passive"))
      (node (ref "SV18") (pin "6") (pinfunction "6_6") (pintype "passive"))
      (node (ref "SV18") (pin "8") (pinfunction "8_8") (pintype "passive"))
      (node (ref "SV2") (pin "10") (pinfunction "10_10") (pintype "passive"))
      (node (ref "SV2") (pin "12") (pinfunction "12_12") (pintype "passive"))
      (node (ref "SV2") (pin "14") (pinfunction "14_14") (pintype "passive"))
      (node (ref "SV2") (pin "16") (pinfunction "16_16") (pintype "passive"))
      (node (ref "SV2") (pin "18") (pinfunction "18_18") (pintype "passive"))
      (node (ref "SV2") (pin "2") (pinfunction "2_2") (pintype "passive"))
      (node (ref "SV2") (pin "20") (pinfunction "20_20") (pintype "passive"))
      (node (ref "SV2") (pin "22") (pinfunction "22_22") (pintype "passive"))
      (node (ref "SV2") (pin "24") (pinfunction "24_24") (pintype "passive"))
      (node (ref "SV2") (pin "26") (pinfunction "26_26") (pintype "passive"))
      (node (ref "SV2") (pin "28") (pinfunction "28_28") (pintype "passive"))
      (node (ref "SV2") (pin "30") (pinfunction "30_30") (pintype "passive"))
      (node (ref "SV2") (pin "32") (pinfunction "32_32") (pintype "passive"))
      (node (ref "SV2") (pin "34") (pinfunction "34_34") (pintype "passive"))
      (node (ref "SV2") (pin "36") (pinfunction "36_36") (pintype "passive"))
      (node (ref "SV2") (pin "38") (pinfunction "38_38") (pintype "passive"))
      (node (ref "SV2") (pin "4") (pinfunction "4_4") (pintype "passive"))
      (node (ref "SV2") (pin "40") (pinfunction "40_40") (pintype "passive"))
      (node (ref "SV2") (pin "6") (pinfunction "6_6") (pintype "passive"))
      (node (ref "SV2") (pin "8") (pinfunction "8_8") (pintype "passive"))
      (node (ref "SV20") (pin "10") (pinfunction "10_10") (pintype "passive"))
      (node (ref "SV20") (pin "12") (pinfunction "12_12") (pintype "passive"))
      (node (ref "SV20") (pin "14") (pinfunction "14_14") (pintype "passive"))
      (node (ref "SV20") (pin "16") (pinfunction "16_16") (pintype "passive"))
      (node (ref "SV20") (pin "18") (pinfunction "18_18") (pintype "passive"))
      (node (ref "SV20") (pin "2") (pinfunction "2_2") (pintype "passive"))
      (node (ref "SV20") (pin "20") (pinfunction "20_20") (pintype "passive"))
      (node (ref "SV20") (pin "22") (pinfunction "22_22") (pintype "passive"))
      (node (ref "SV20") (pin "24") (pinfunction "24_24") (pintype "passive"))
      (node (ref "SV20") (pin "26") (pinfunction "26_26") (pintype "passive"))
      (node (ref "SV20") (pin "28") (pinfunction "28_28") (pintype "passive"))
      (node (ref "SV20") (pin "30") (pinfunction "30_30") (pintype "passive"))
      (node (ref "SV20") (pin "32") (pinfunction "32_32") (pintype "passive"))
      (node (ref "SV20") (pin "34") (pinfunction "34_34") (pintype "passive"))
      (node (ref "SV20") (pin "36") (pinfunction "36_36") (pintype "passive"))
      (node (ref "SV20") (pin "38") (pinfunction "38_38") (pintype "passive"))
      (node (ref "SV20") (pin "4") (pinfunction "4_4") (pintype "passive"))
      (node (ref "SV20") (pin "40") (pinfunction "40_40") (pintype "passive"))
      (node (ref "SV20") (pin "6") (pinfunction "6_6") (pintype "passive"))
      (node (ref "SV20") (pin "8") (pinfunction "8_8") (pintype "passive"))
      (node (ref "SV8") (pin "10") (pinfunction "10_10") (pintype "passive"))
      (node (ref "SV8") (pin "12") (pinfunction "12_12") (pintype "passive"))
      (node (ref "SV8") (pin "14") (pinfunction "14_14") (pintype "passive"))
      (node (ref "SV8") (pin "16") (pinfunction "16_16") (pintype "passive"))
      (node (ref "SV8") (pin "18") (pinfunction "18_18") (pintype "passive"))
      (node (ref "SV8") (pin "2") (pinfunction "2_2") (pintype "passive"))
      (node (ref "SV8") (pin "20") (pinfunction "20_20") (pintype "passive"))
      (node (ref "SV8") (pin "22") (pinfunction "22_22") (pintype "passive"))
      (node (ref "SV8") (pin "24") (pinfunction "24_24") (pintype "passive"))
      (node (ref "SV8") (pin "26") (pinfunction "26_26") (pintype "passive"))
      (node (ref "SV8") (pin "28") (pinfunction "28_28") (pintype "passive"))
      (node (ref "SV8") (pin "30") (pinfunction "30_30") (pintype "passive"))
      (node (ref "SV8") (pin "32") (pinfunction "32_32") (pintype "passive"))
      (node (ref "SV8") (pin "34") (pinfunction "34_34") (pintype "passive"))
      (node (ref "SV8") (pin "36") (pinfunction "36_36") (pintype "passive"))
      (node (ref "SV8") (pin "4") (pinfunction "4_4") (pintype "passive"))
      (node (ref "SV8") (pin "6") (pinfunction "6_6") (pintype "passive"))
      (node (ref "SV8") (pin "8") (pinfunction "8_8") (pintype "passive"))
      (node (ref "U$1") (pin "A2") (pinfunction "1_A2") (pintype "bidirectional"))
      (node (ref "U$3") (pin "A2") (pinfunction "P$1_A2") (pintype "passive"))
    )
  )
)
